# outdoor-sensor.net
KiCad netlist of a schematic drawn in EAGLE
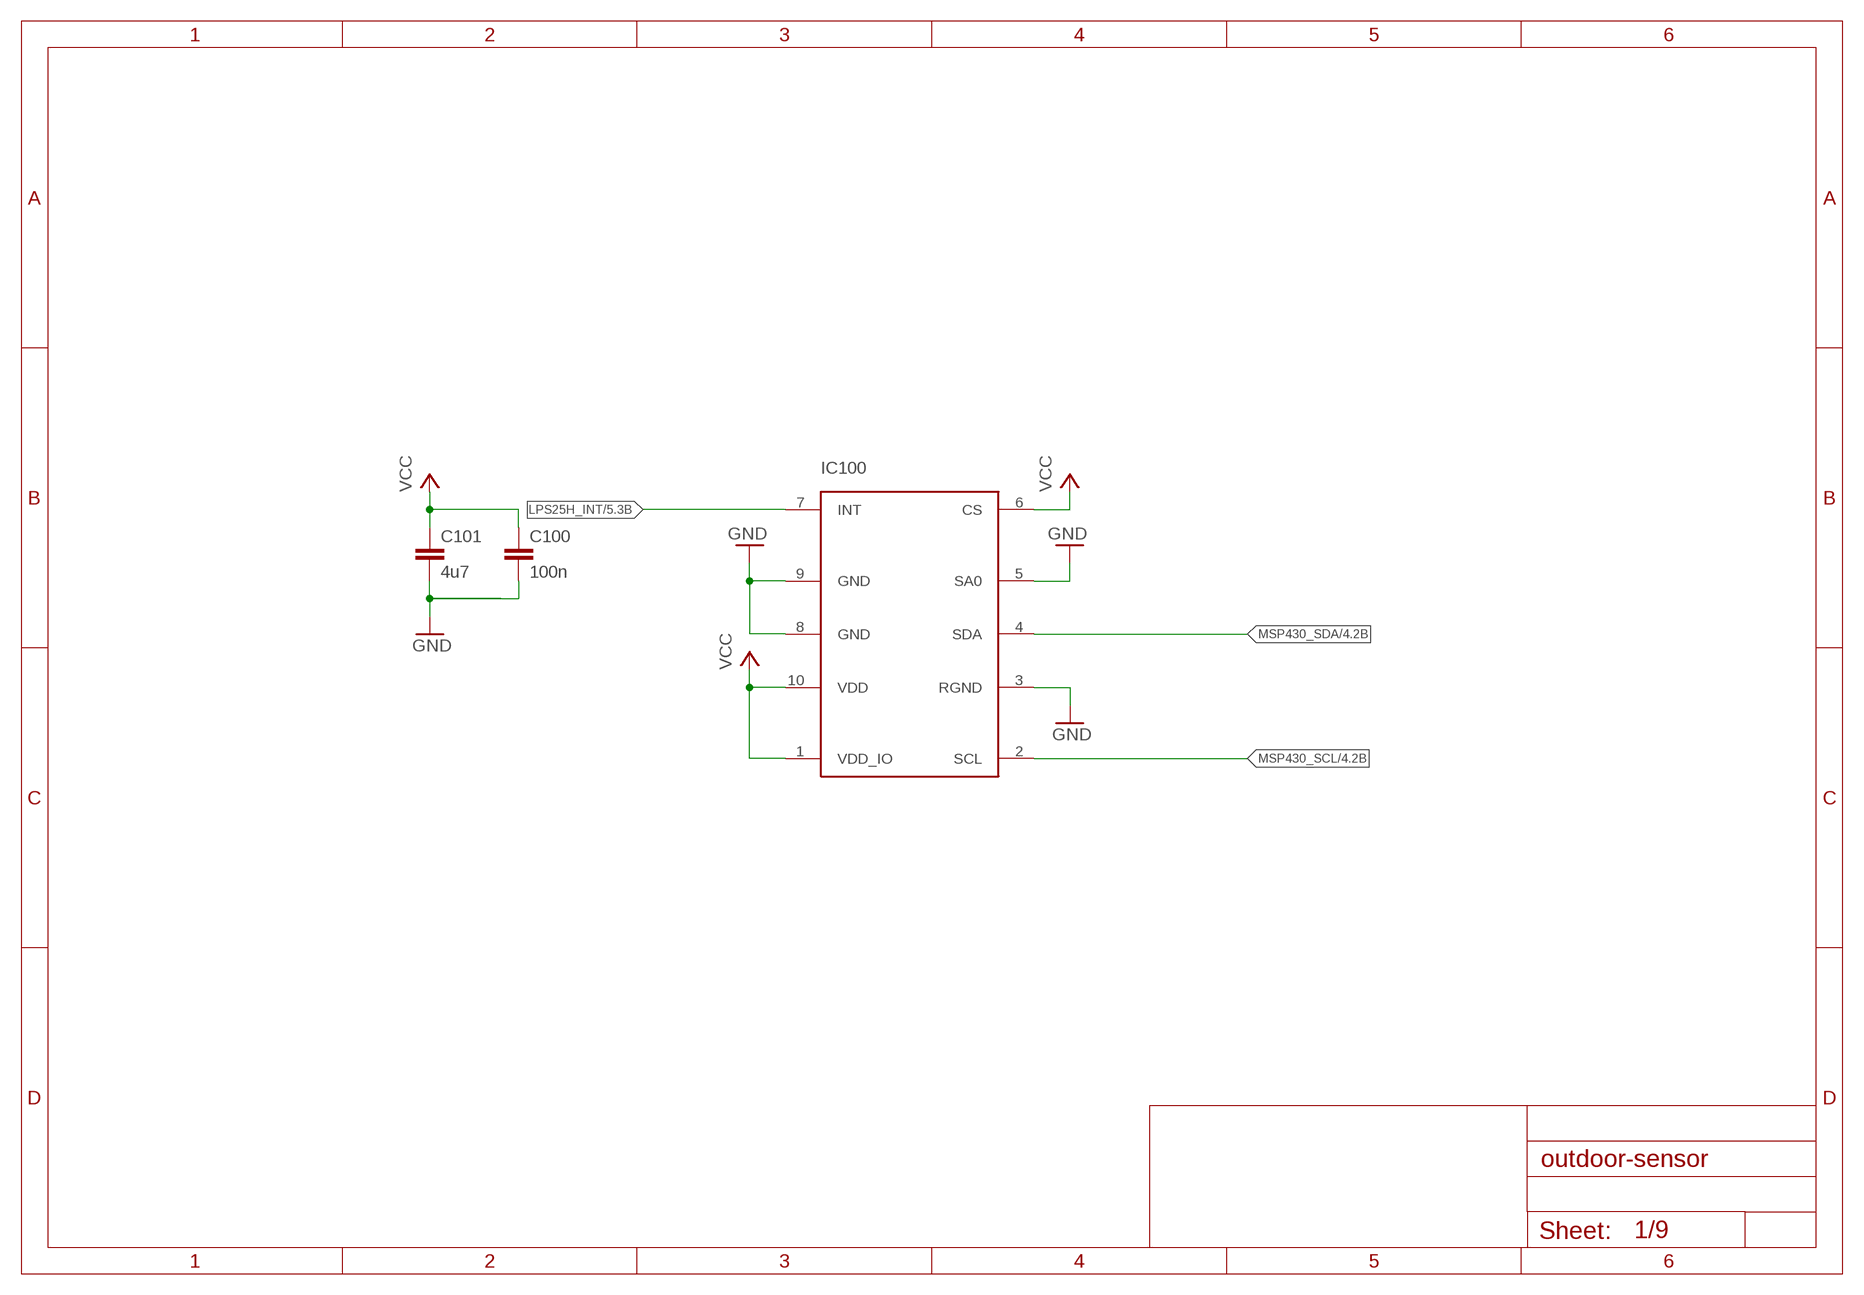
[diagram p0: schematic, sheet 1]
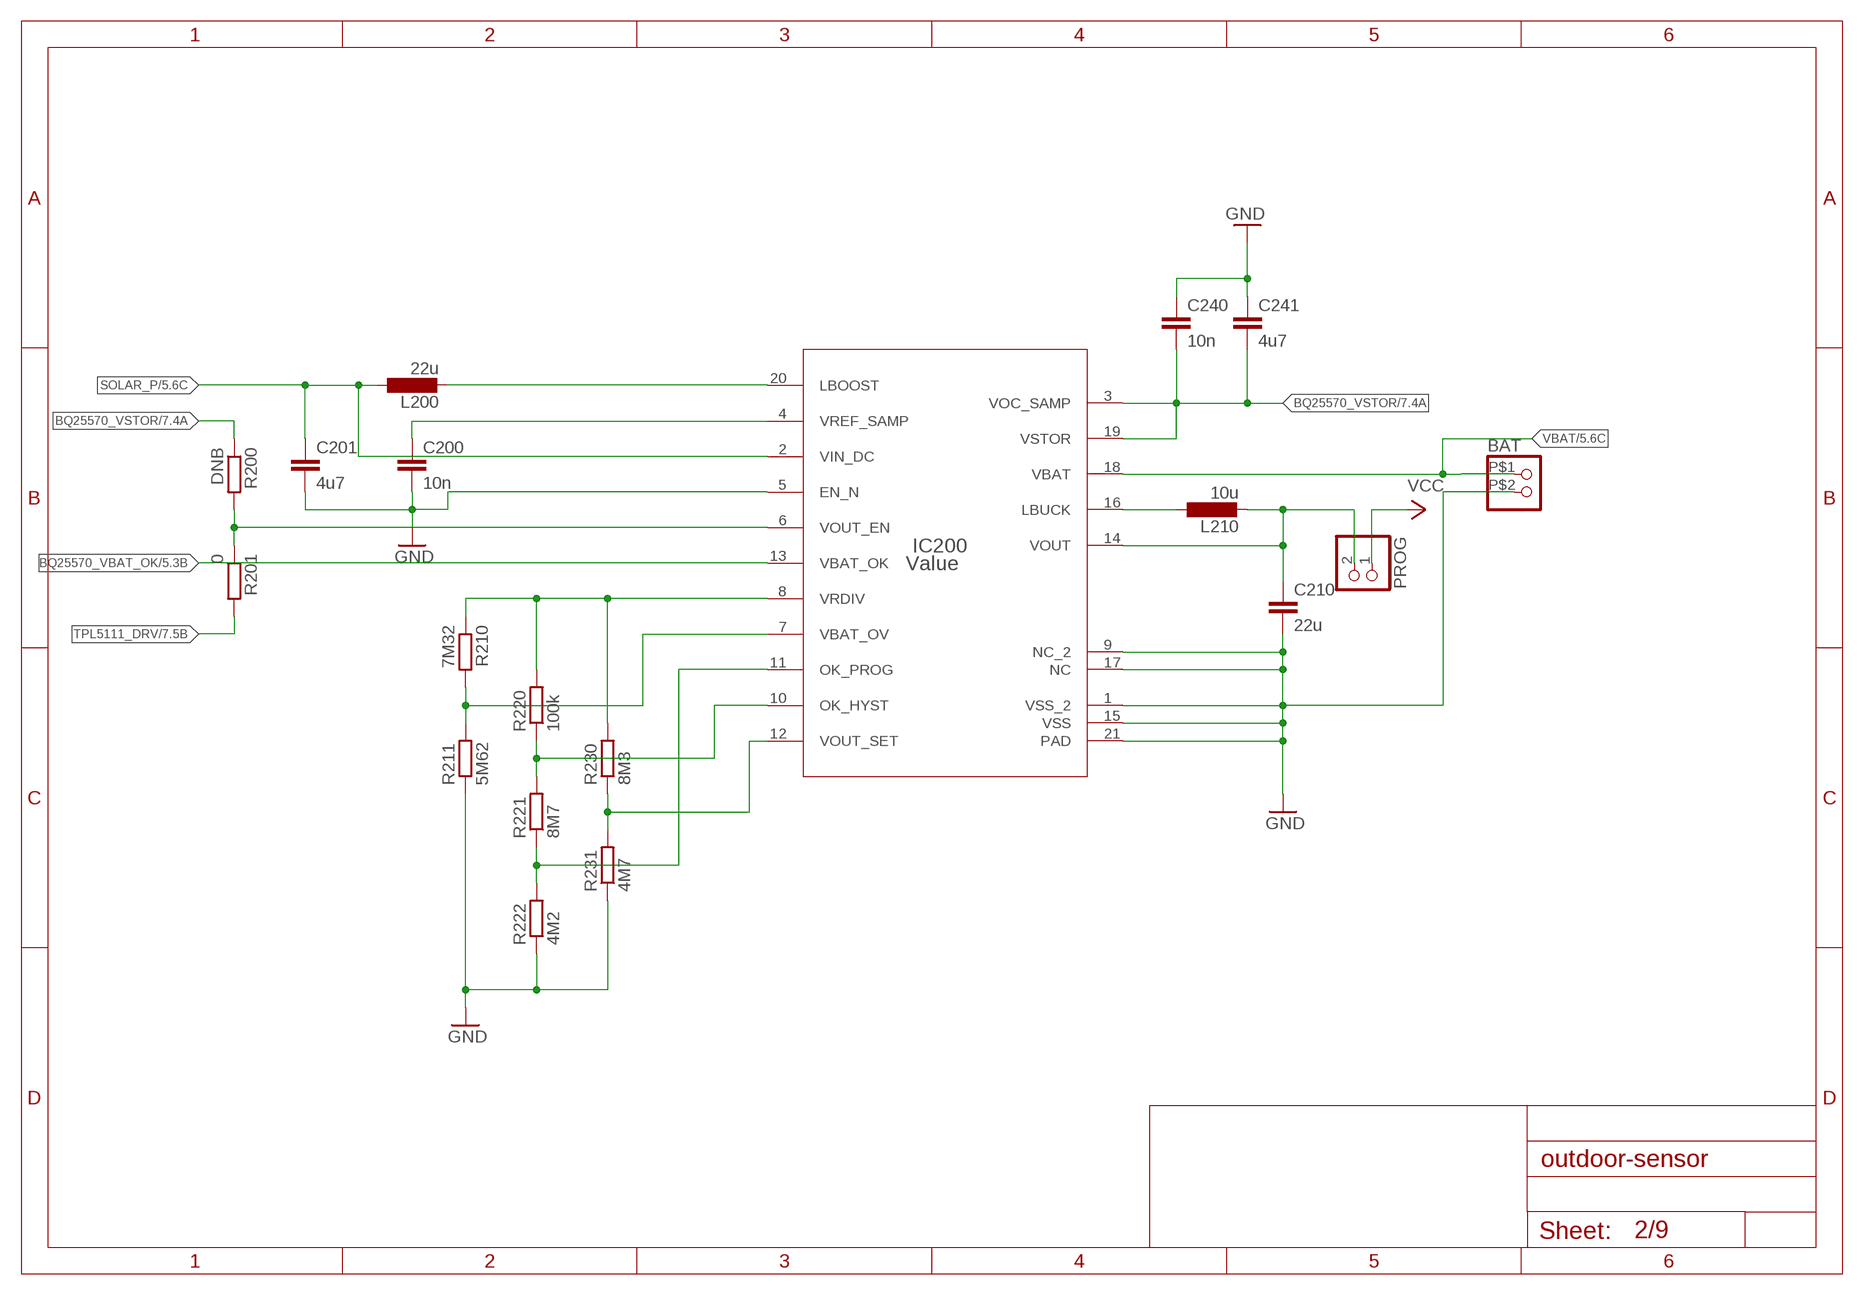
[diagram p1: schematic, sheet 2]
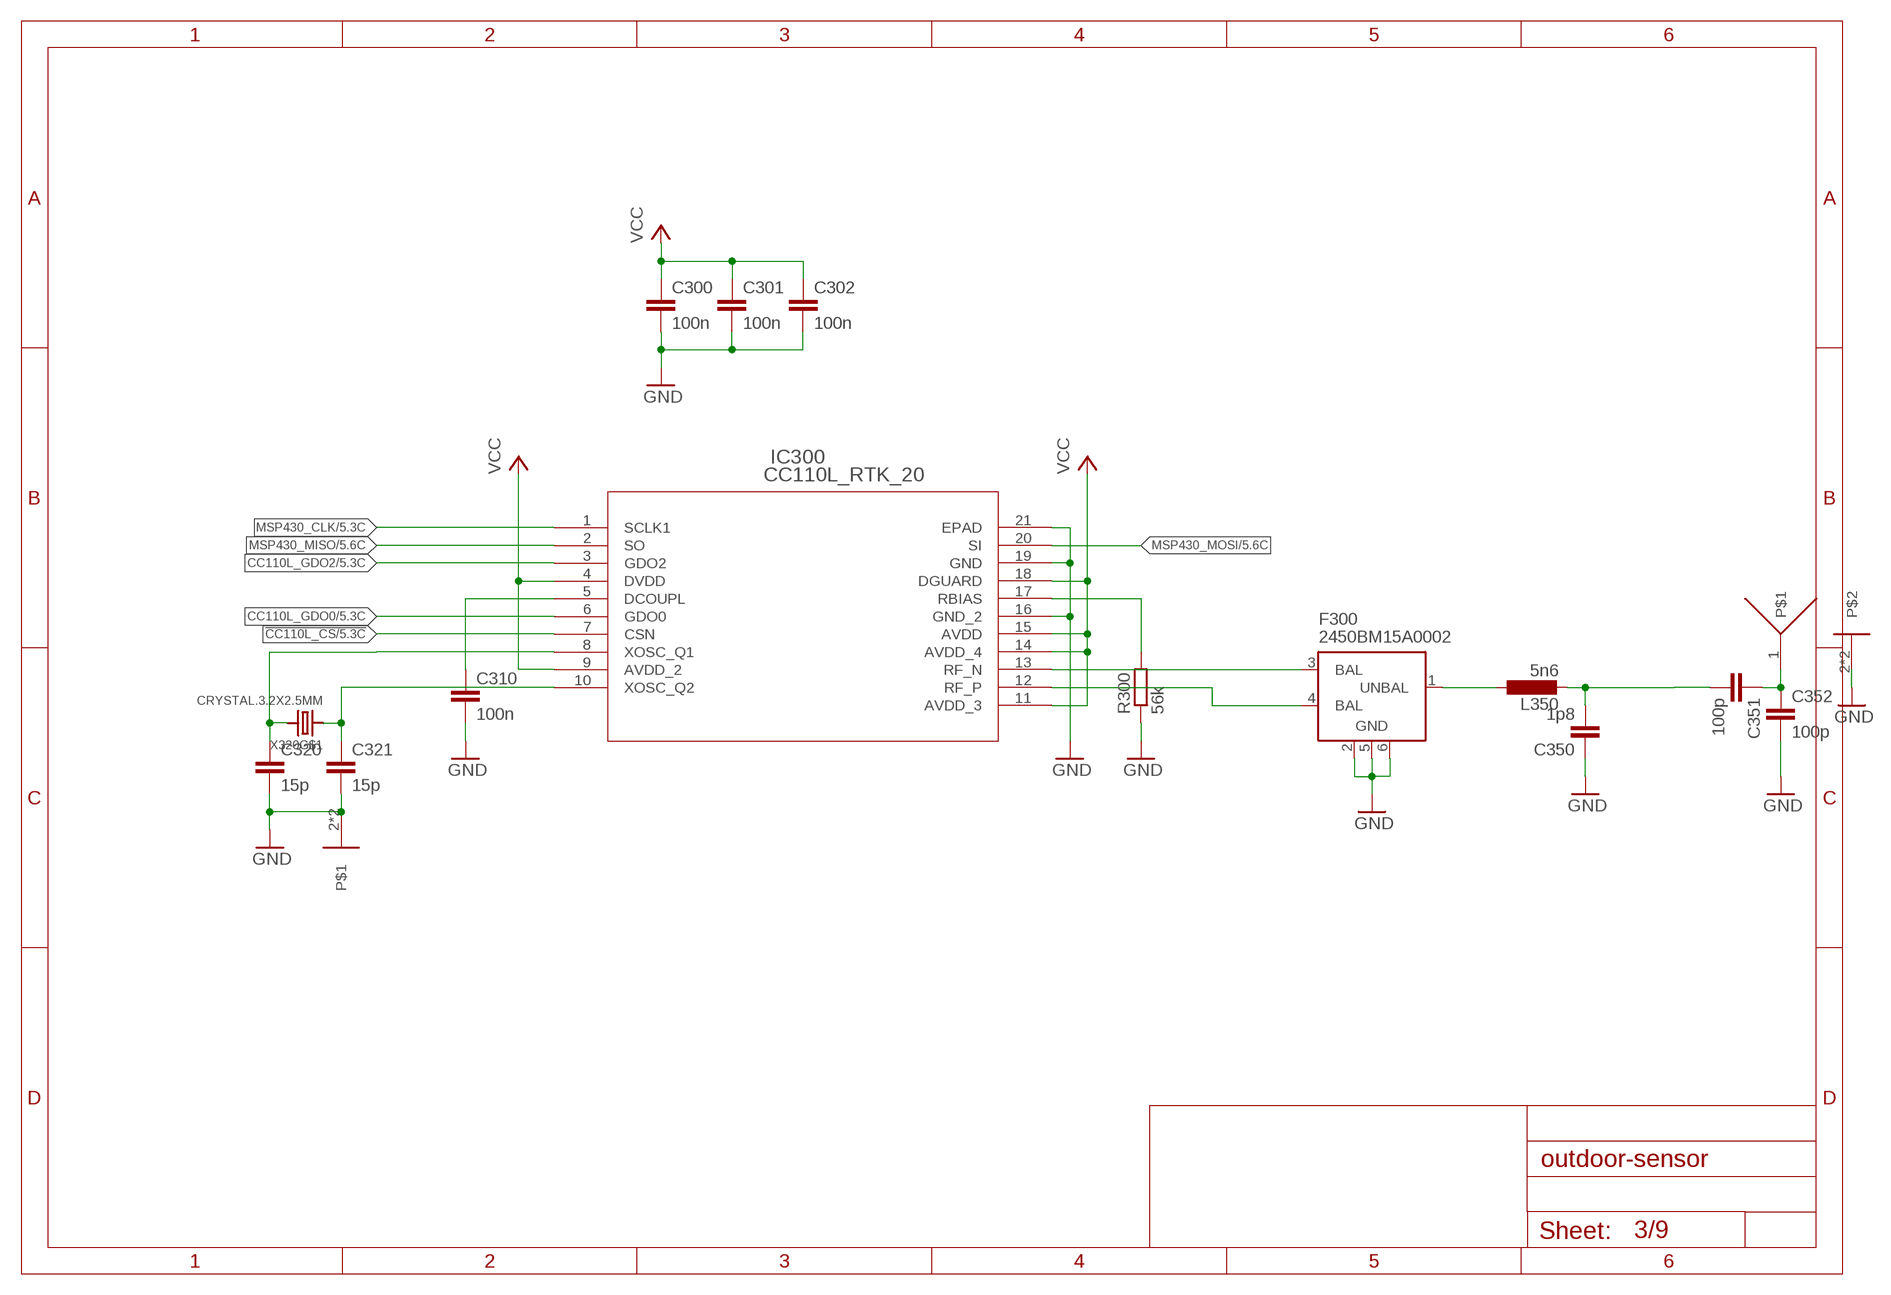
[diagram p2: schematic, sheet 3]
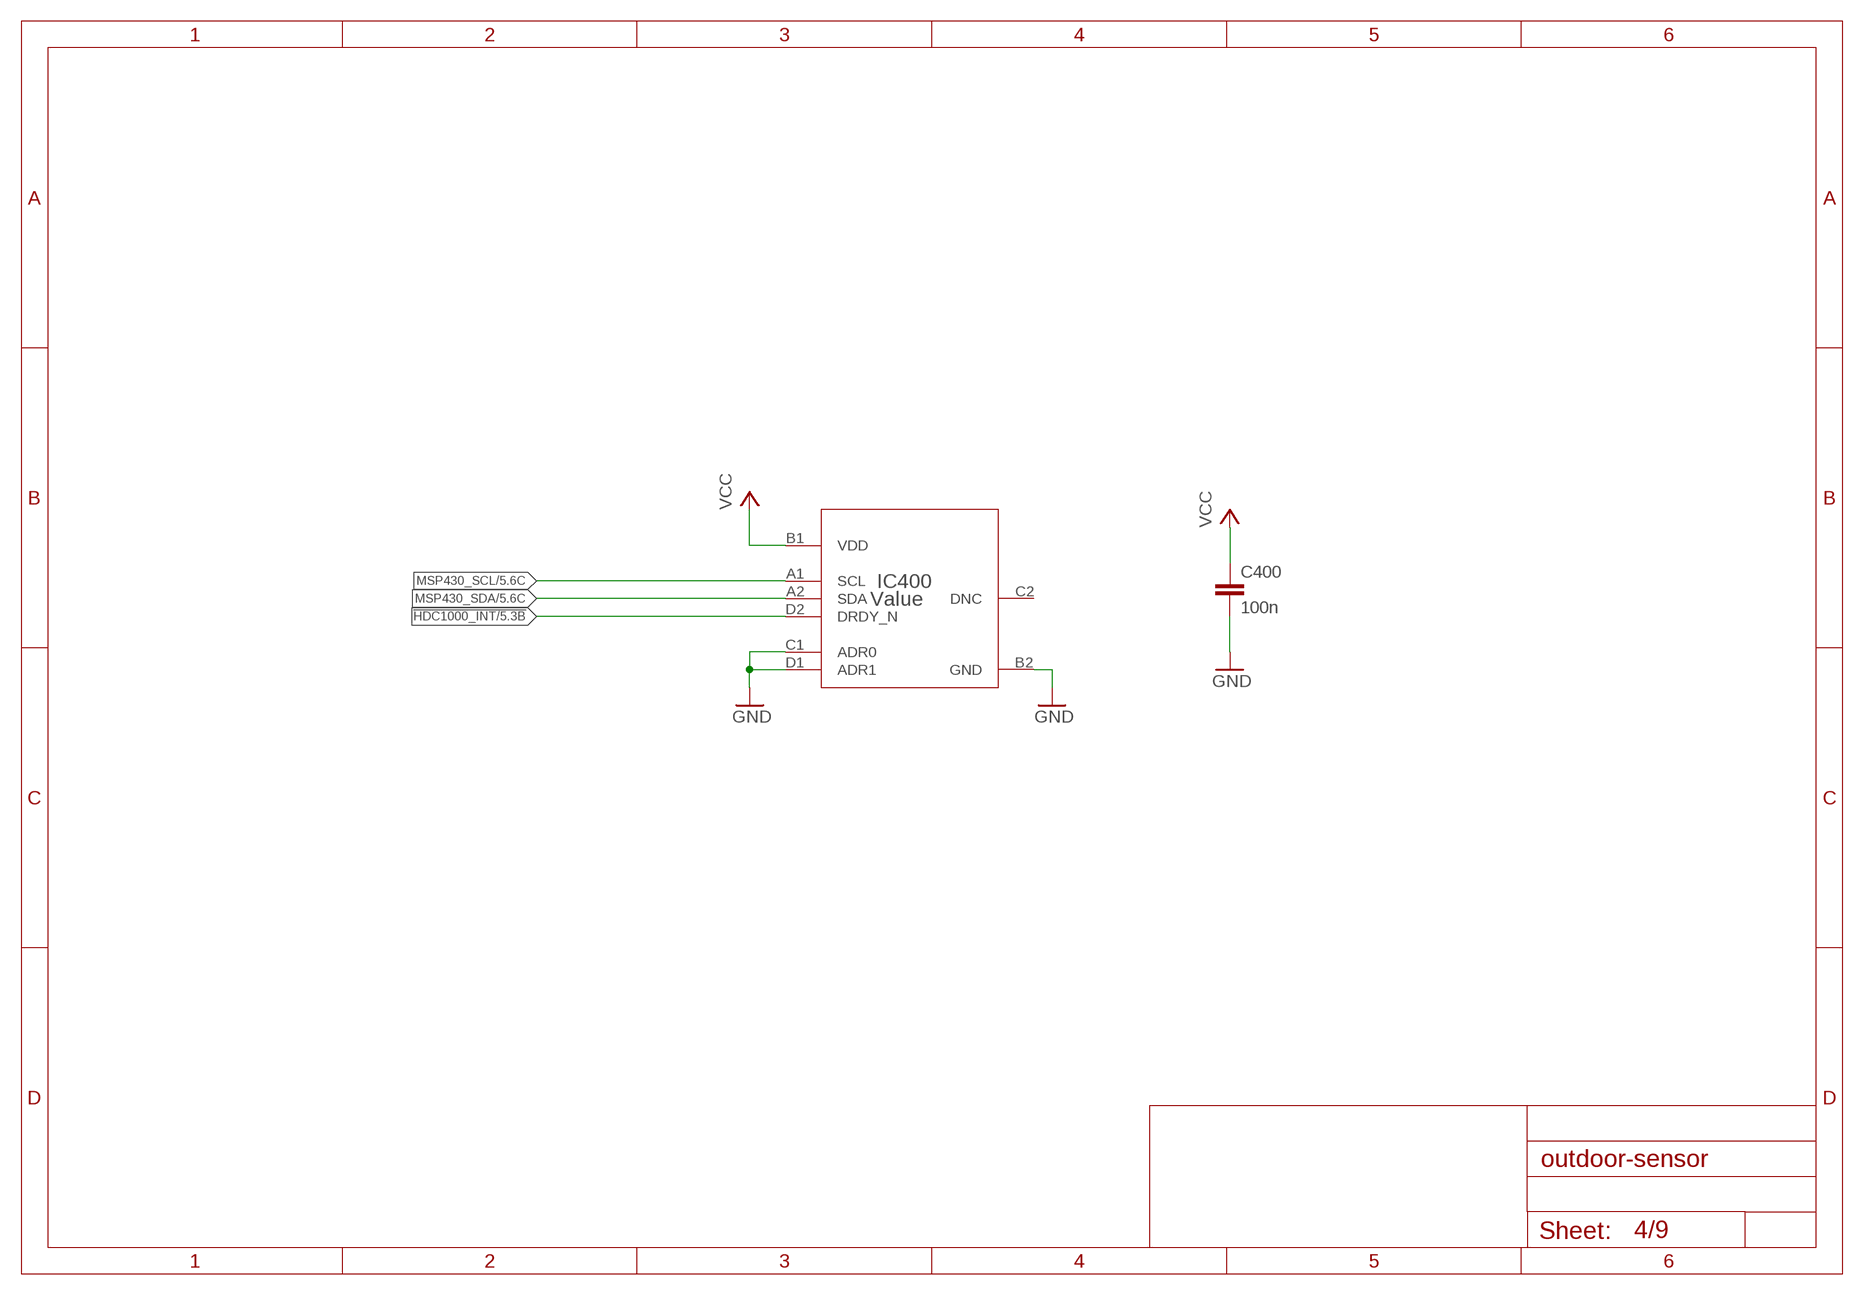
[diagram p3: schematic, sheet 4]
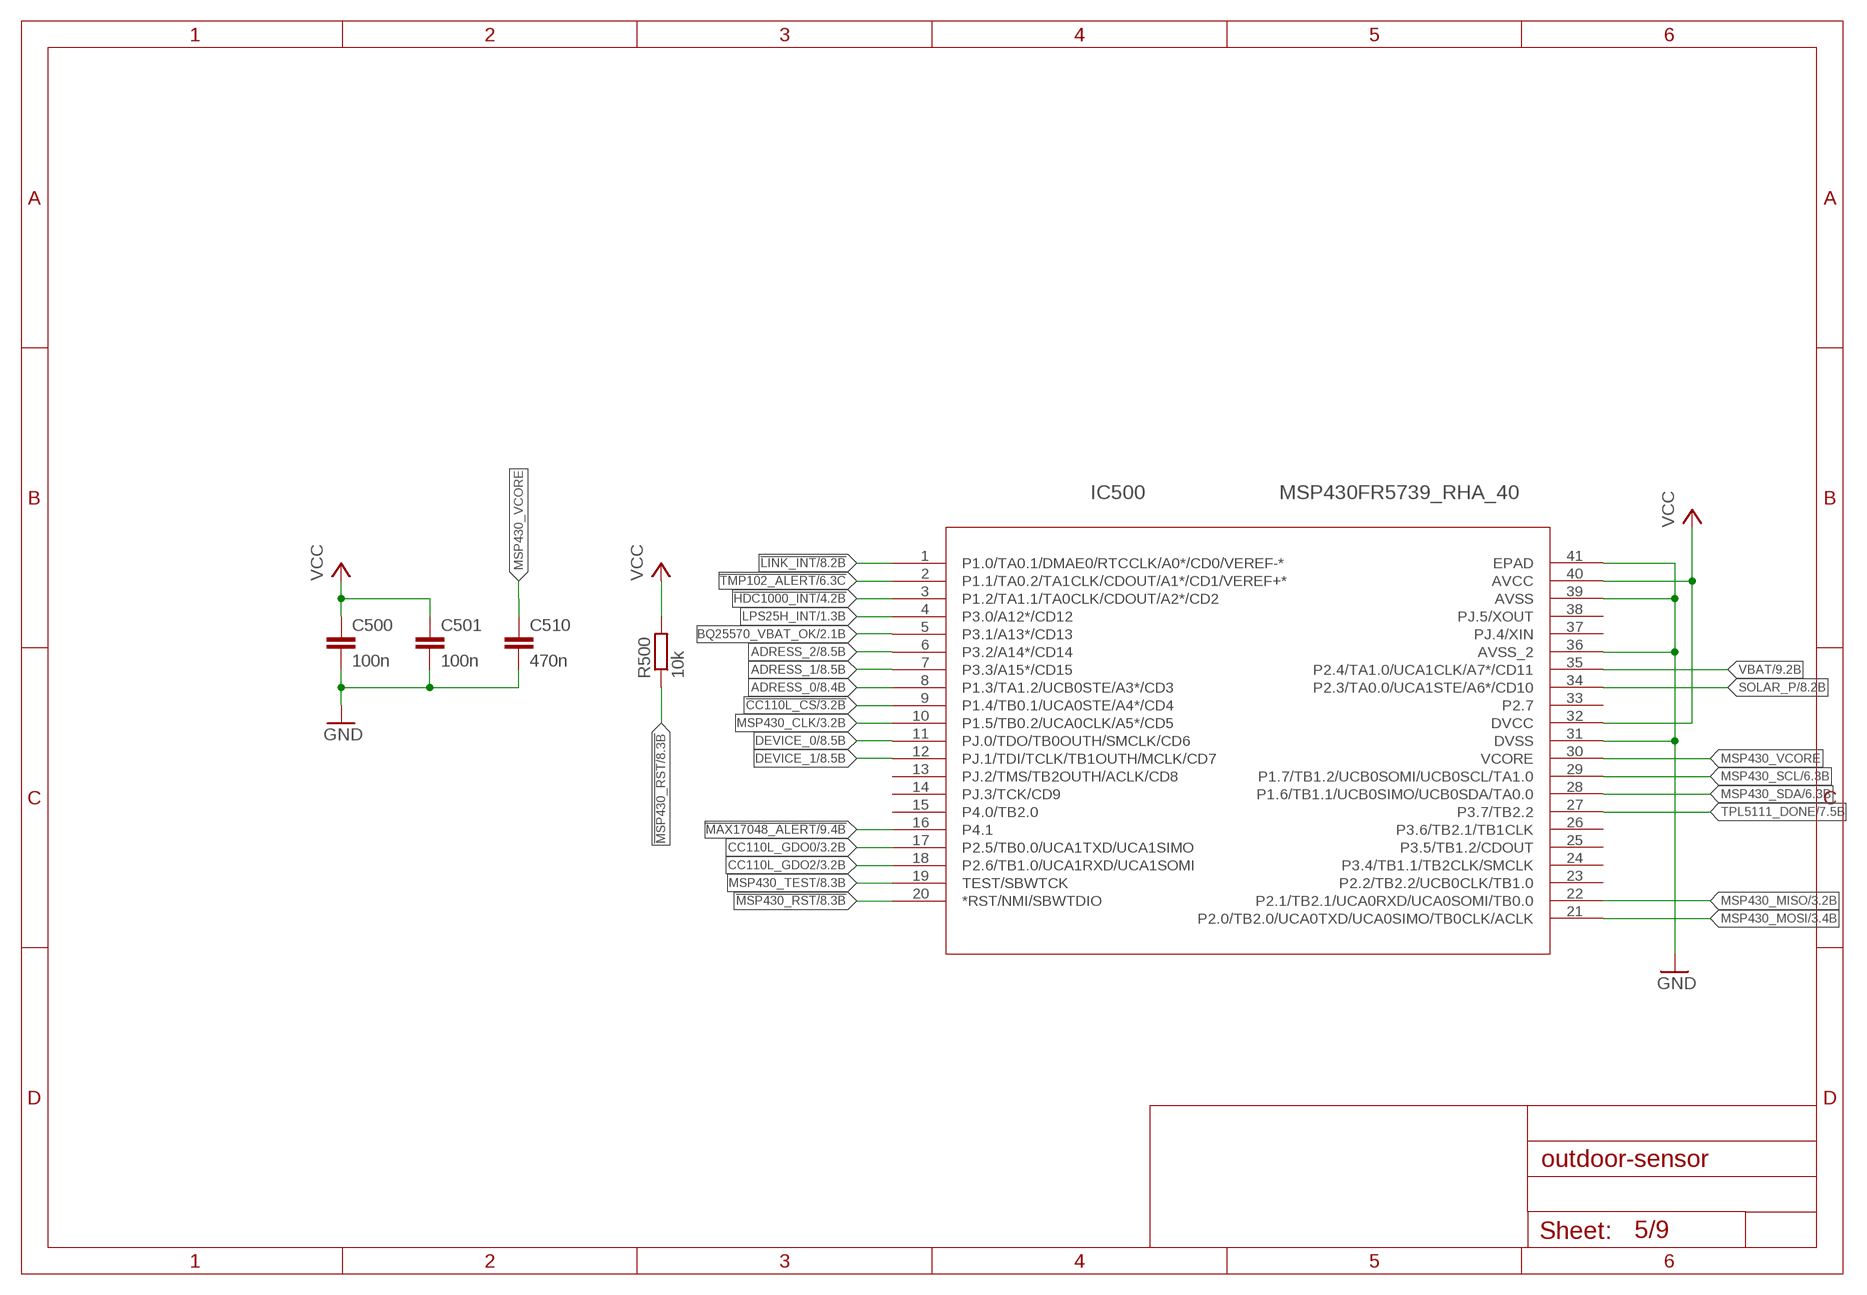
[diagram p4: schematic, sheet 5]
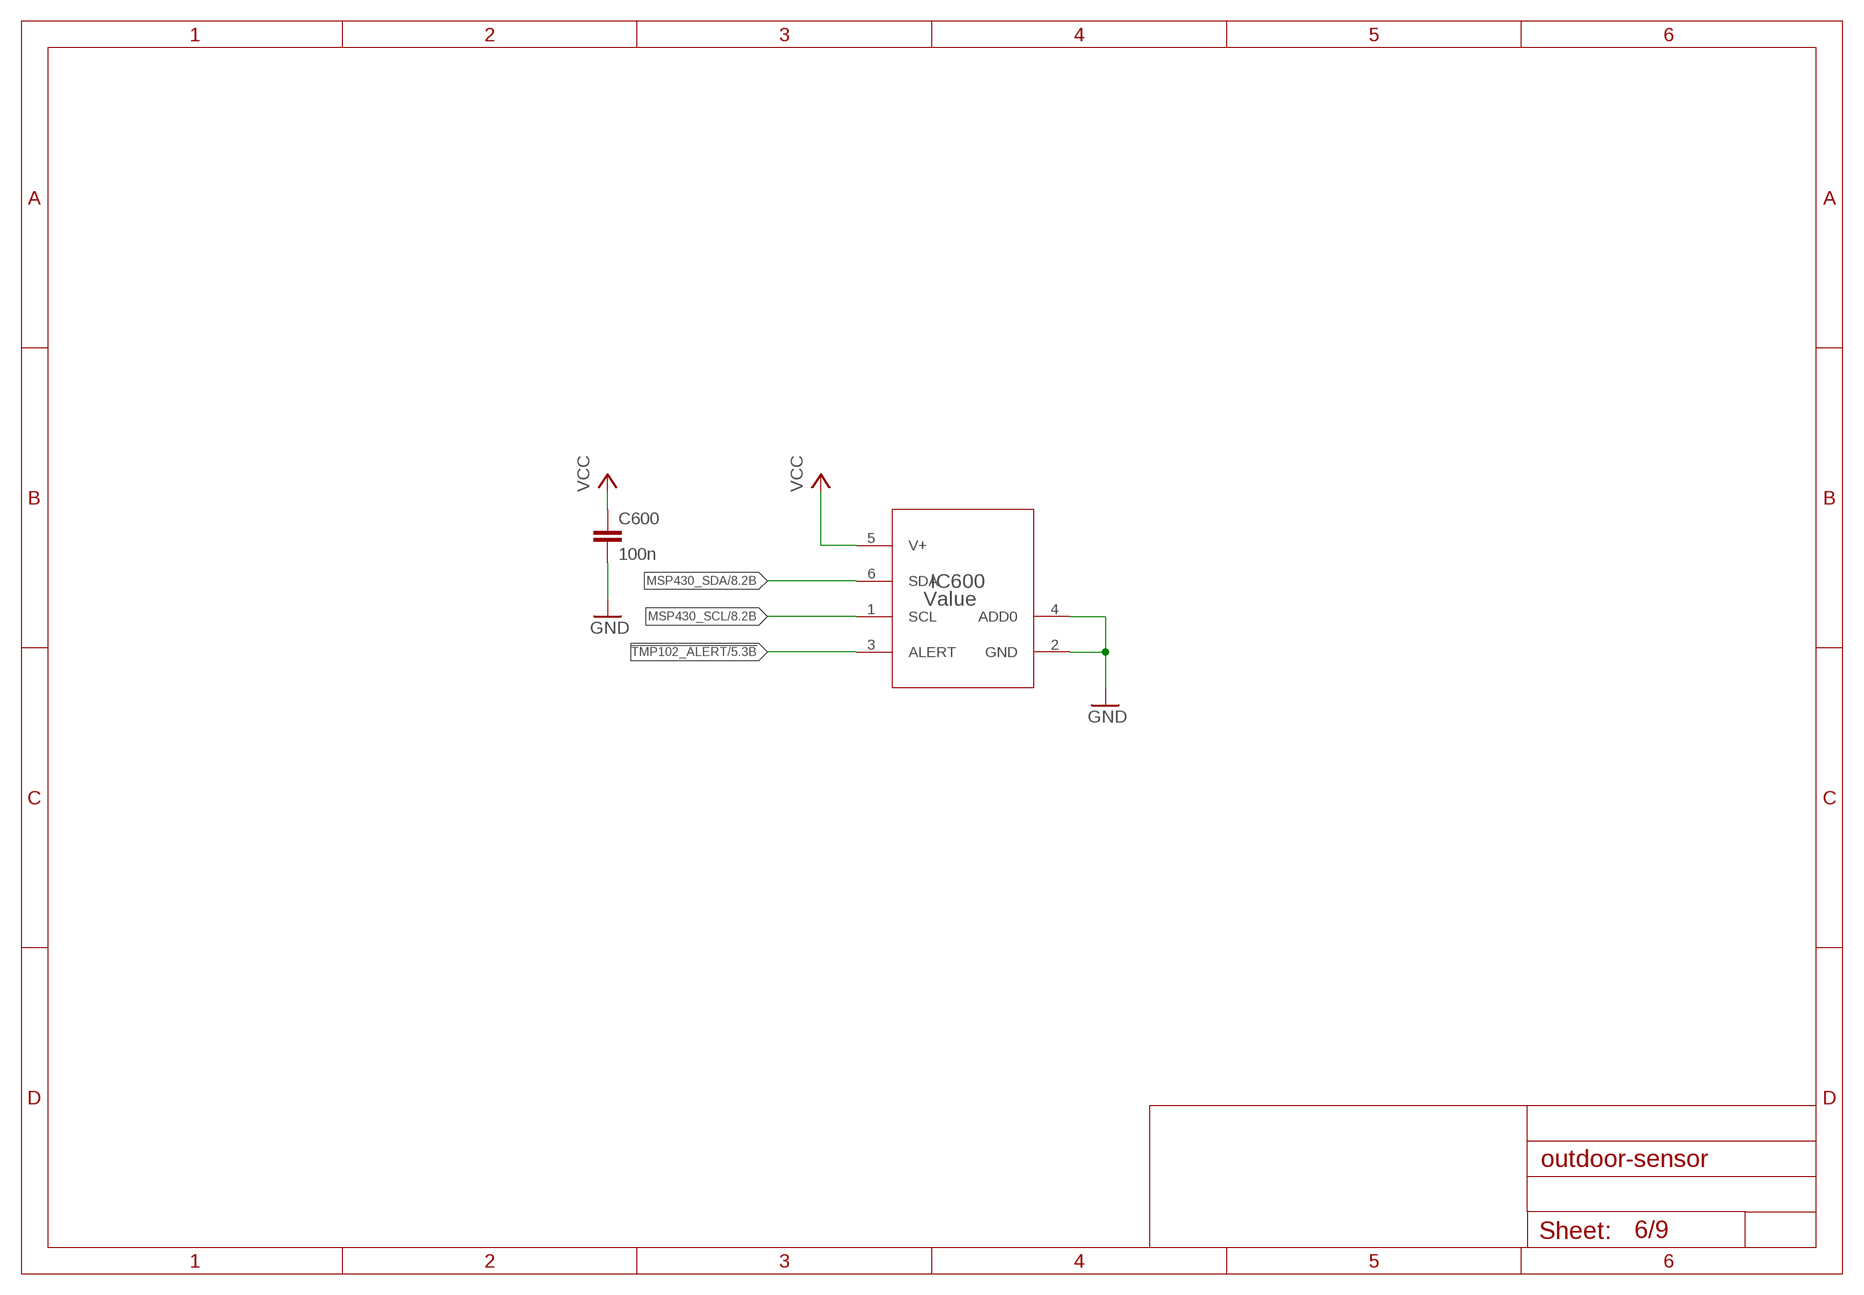
[diagram p5: schematic, sheet 6]
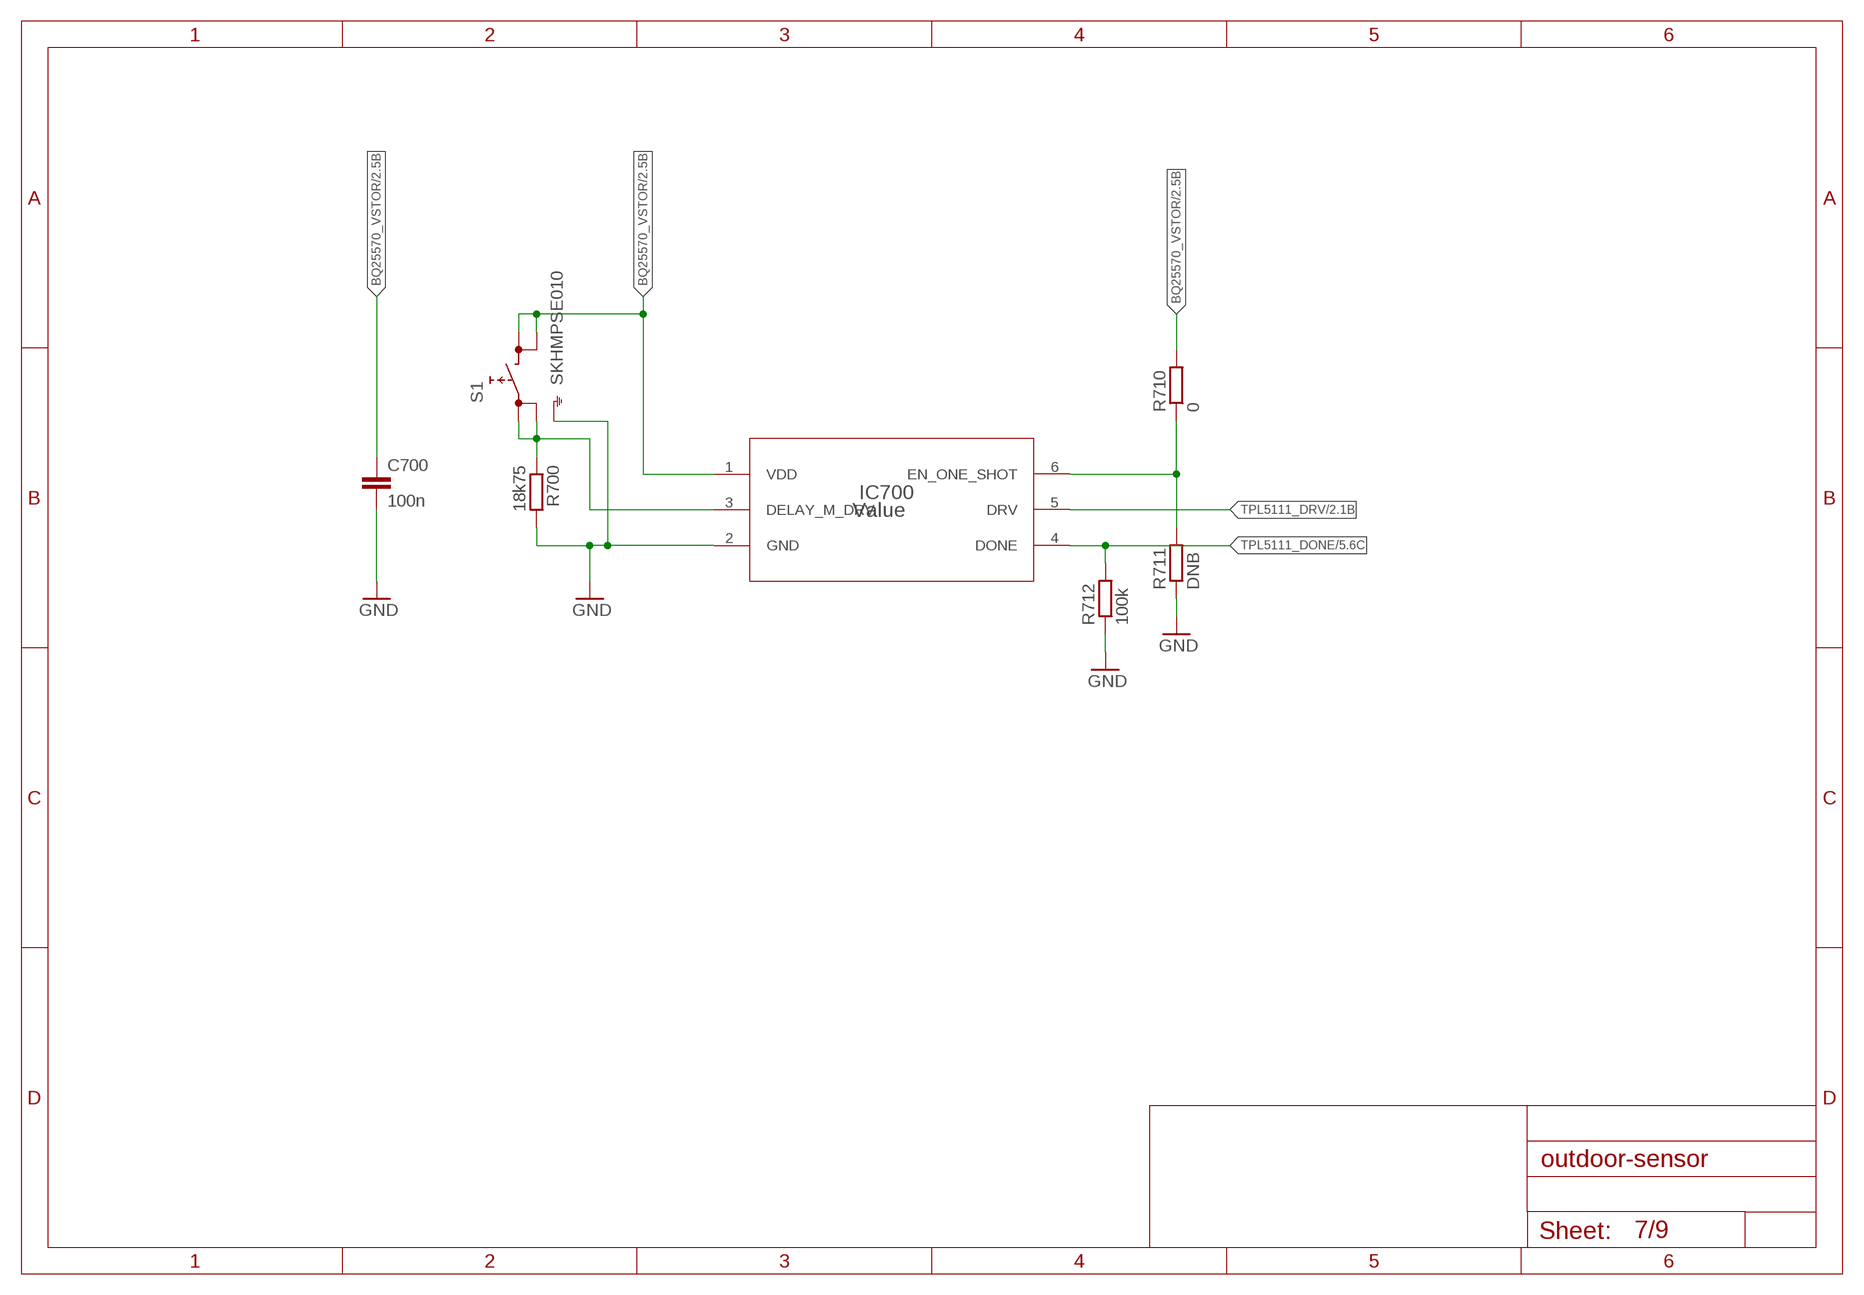
[diagram p6: schematic, sheet 7]
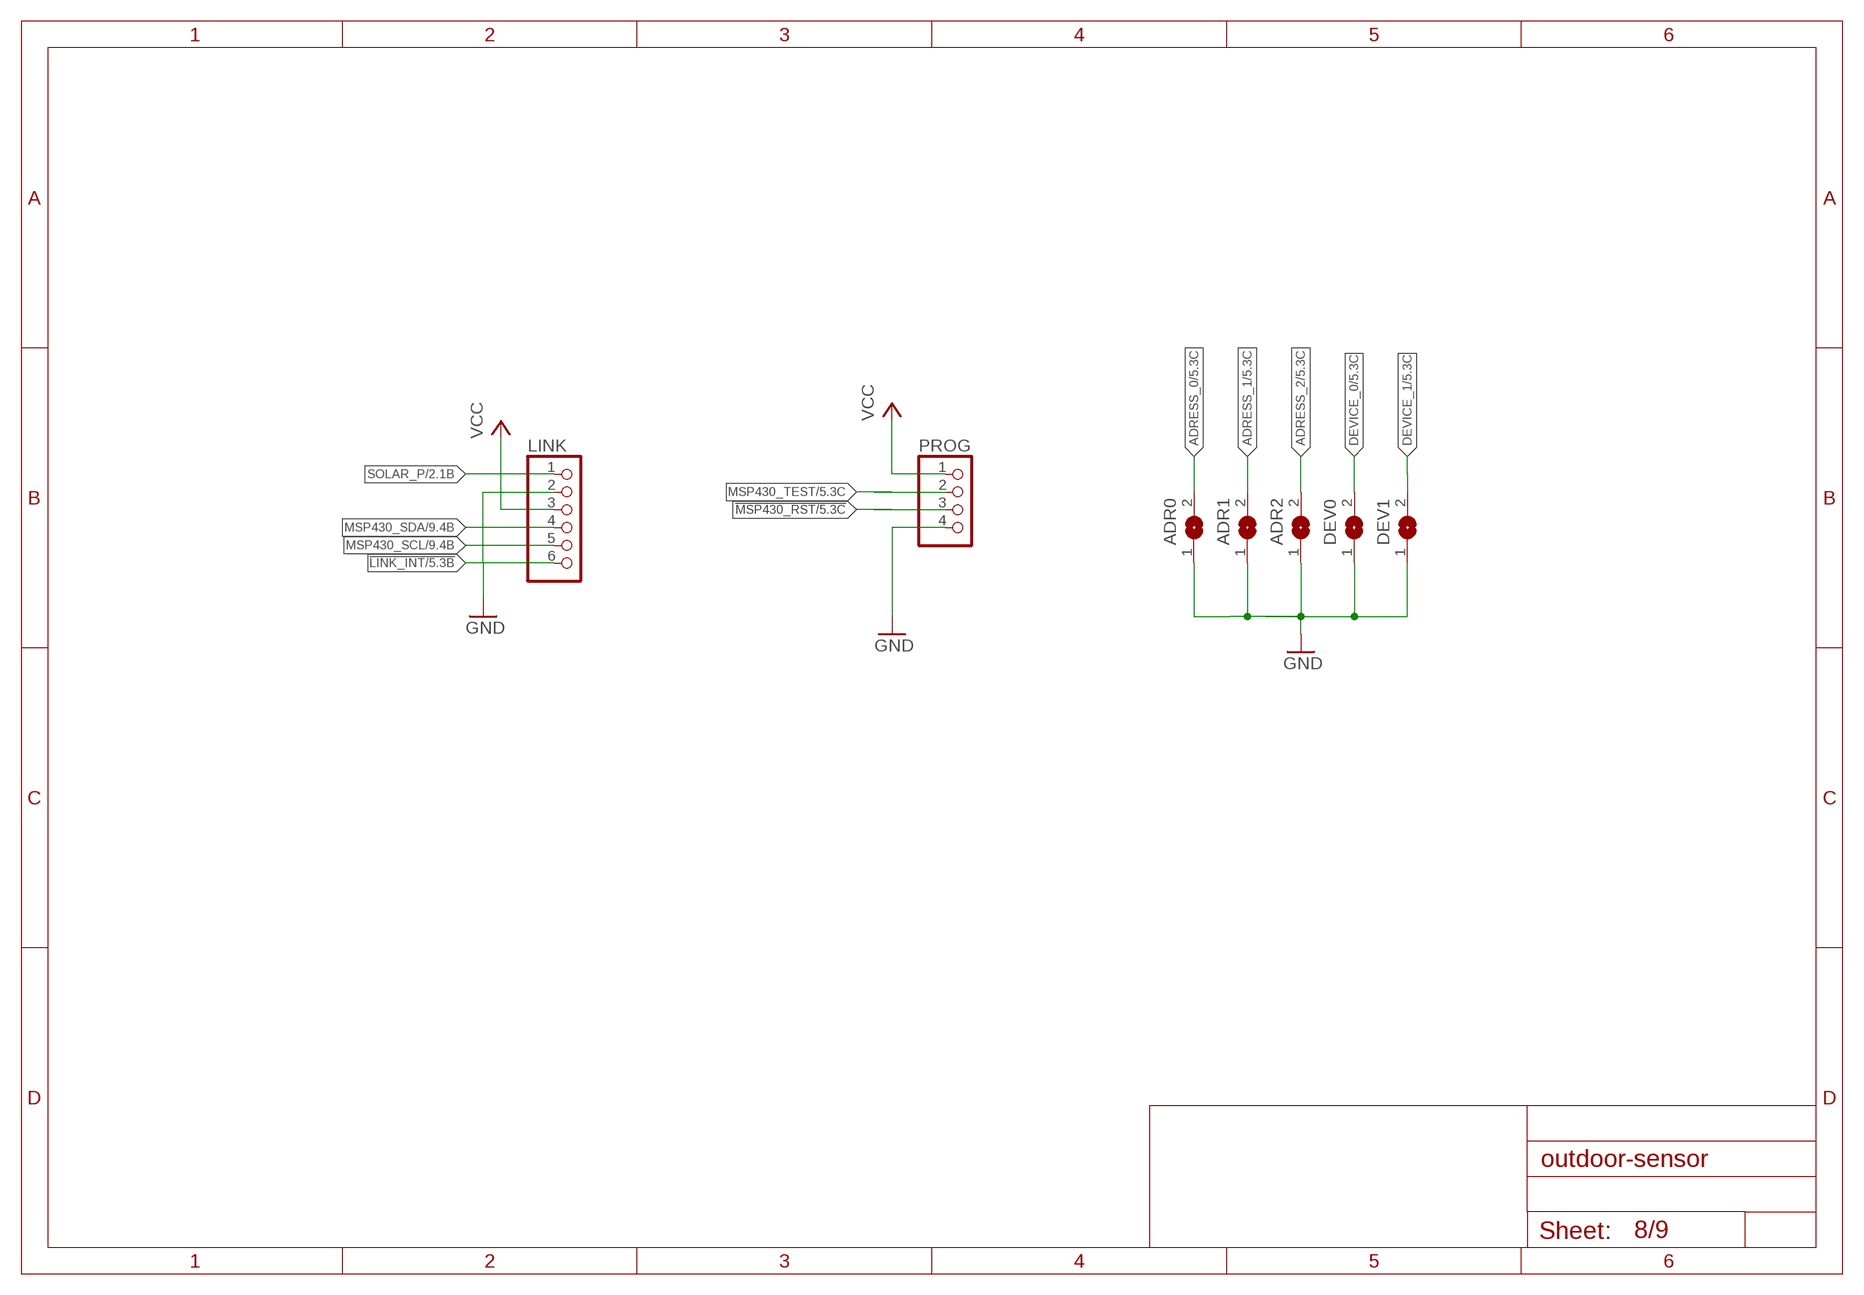
[diagram p7: schematic, sheet 8]
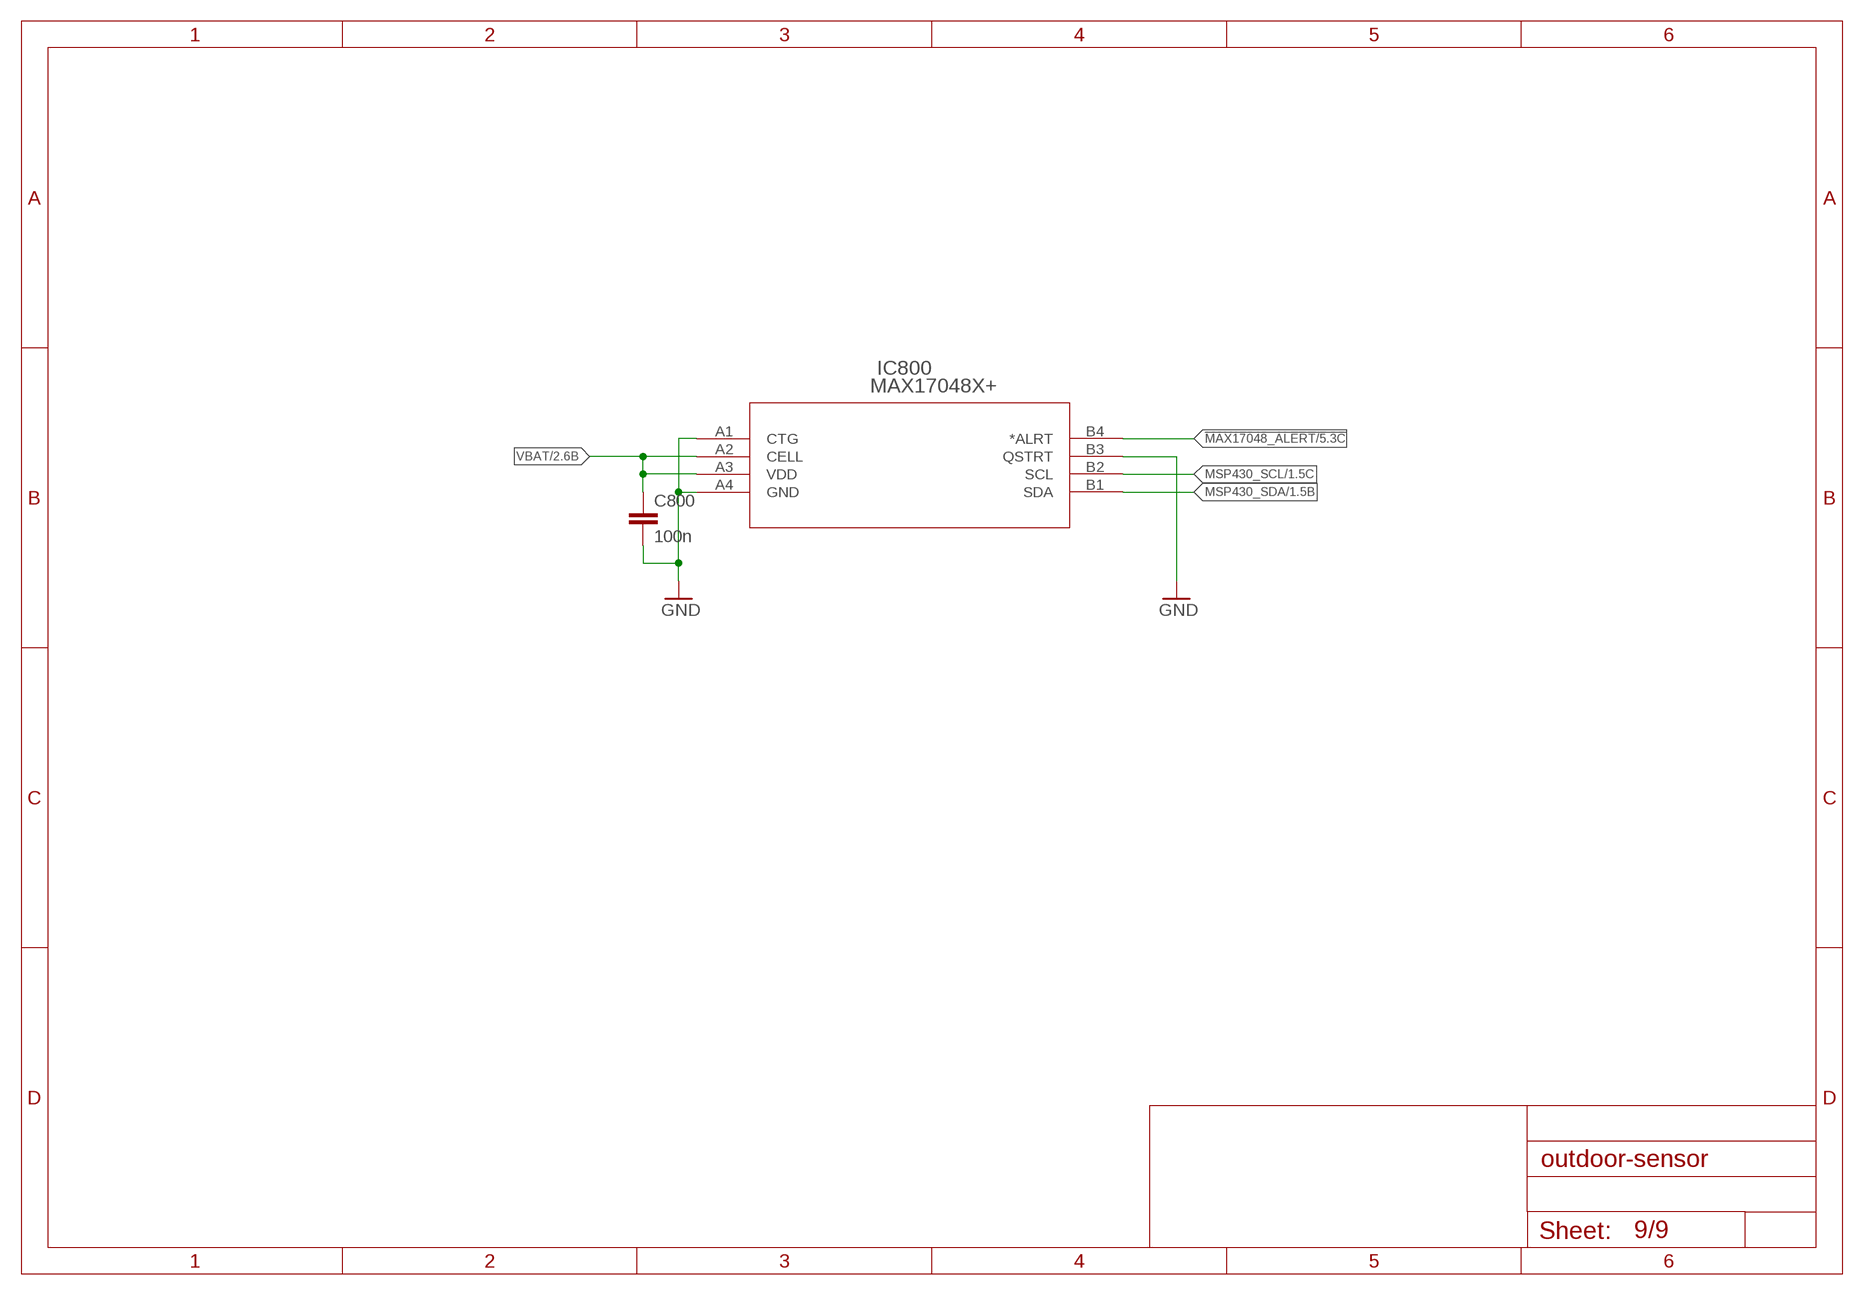
[diagram p8: schematic, sheet 9]

(export (version "E")
  (design (tool "Eeschema 10.0.6"))
  (components
    (comp (ref "ADR0")
      (value "SJW")
      (footprint "eagle-import:SJW")
      (libsource (lib "eagle-import") (part "SJW"))
    )
    (comp (ref "ADR1")
      (value "SJW")
      (footprint "eagle-import:SJW")
      (libsource (lib "eagle-import") (part "SJW"))
    )
    (comp (ref "ADR2")
      (value "SJW")
      (footprint "eagle-import:SJW")
      (libsource (lib "eagle-import") (part "SJW"))
    )
    (comp (ref "DEV0")
      (value "SJW")
      (footprint "eagle-import:SJW")
      (libsource (lib "eagle-import") (part "SJW"))
    )
    (comp (ref "DEV1")
      (value "SJW")
      (footprint "eagle-import:SJW")
      (libsource (lib "eagle-import") (part "SJW"))
    )
    (comp (ref "LINK")
      (value "PINHD-1X6")
      (footprint "eagle-import:1X06")
      (libsource (lib "eagle-import") (part "PINHD-1X6"))
    )
    (comp (ref "PROG")
      (value "PINHD-1X4")
      (footprint "eagle-import:1X04")
      (libsource (lib "eagle-import") (part "PINHD-1X4"))
    )
    (comp (ref "!PROG")
      (value "PINHD-1X2")
      (footprint "eagle-import:1X02")
      (libsource (lib "eagle-import") (part "PINHD-1X2"))
    )
    (comp (ref "BAT")
      (value "PINHD-1X2IPBS-102-01-T-S-GP")
      (footprint "eagle-import:IPBS-102-01-T-S-GP")
      (libsource (lib "eagle-import") (part "PINHD-1X2IPBS-102-01-T-S-GP"))
    )
    (comp (ref "C200")
      (value "10n")
      (footprint "eagle-import:C0603")
      (libsource (lib "eagle-import") (part "C-EUC0603"))
    )
    (comp (ref "C201")
      (value "4u7")
      (footprint "eagle-import:C0603")
      (libsource (lib "eagle-import") (part "C-EUC0603"))
    )
    (comp (ref "C210")
      (value "22u")
      (footprint "eagle-import:C0603")
      (fields (field (name "MF") "AVX") (field (name "MPN") "06034D226MAT2A"))
      (libsource (lib "eagle-import") (part "C-EUC0603"))
    )
    (comp (ref "C240")
      (value "10n")
      (footprint "eagle-import:C0603")
      (libsource (lib "eagle-import") (part "C-EUC0603"))
    )
    (comp (ref "C241")
      (value "4u7")
      (footprint "eagle-import:C0603")
      (libsource (lib "eagle-import") (part "C-EUC0603"))
    )
    (comp (ref "IC200")
      (value "Value")
      (footprint "eagle-import:RGR0020A")
      (fields
        (field (name "ALTERNATEPARTNUMBER") "BQ25570RGRT")
        (field (name "MANUFACTURER") "Texas Instruments")
        (field (name "PARTNUMBER") "BQ25570RGRR")
      )
      (libsource (lib "eagle-import") (part "BQ25570RGRR"))
    )
    (comp (ref "L200")
      (value "22u")
      (footprint "eagle-import:L3944")
      (libsource (lib "eagle-import") (part "L-EUL3944"))
    )
    (comp (ref "L210")
      (value "10u")
      (footprint "eagle-import:L2.5X2.0")
      (libsource (lib "eagle-import") (part "L-EUM"))
    )
    (comp (ref "R200")
      (value "DNB")
      (footprint "eagle-import:R0603")
      (libsource (lib "eagle-import") (part "R-EU_R0603"))
    )
    (comp (ref "R201")
      (value "0")
      (footprint "eagle-import:R0603")
      (libsource (lib "eagle-import") (part "R-EU_R0603"))
    )
    (comp (ref "R210")
      (value "7M32")
      (footprint "eagle-import:R0603")
      (libsource (lib "eagle-import") (part "R-EU_R0603"))
    )
    (comp (ref "R211")
      (value "5M62")
      (footprint "eagle-import:R0603")
      (libsource (lib "eagle-import") (part "R-EU_R0603"))
    )
    (comp (ref "R220")
      (value "100k")
      (footprint "eagle-import:R0603")
      (libsource (lib "eagle-import") (part "R-EU_R0603"))
    )
    (comp (ref "R221")
      (value "8M7")
      (footprint "eagle-import:R0603")
      (libsource (lib "eagle-import") (part "R-EU_R0603"))
    )
    (comp (ref "R222")
      (value "4M2")
      (footprint "eagle-import:R0603")
      (libsource (lib "eagle-import") (part "R-EU_R0603"))
    )
    (comp (ref "R230")
      (value "8M3")
      (footprint "eagle-import:R0603")
      (libsource (lib "eagle-import") (part "R-EU_R0603"))
    )
    (comp (ref "R231")
      (value "4M7")
      (footprint "eagle-import:R0603")
      (libsource (lib "eagle-import") (part "R-EU_R0603"))
    )
    (comp (ref "C500")
      (value "100n")
      (footprint "eagle-import:C0603")
      (fields (field (name "MF") "STMICROELECTRONICS") (field (name "MPN") "STP100NF04"))
      (libsource (lib "eagle-import") (part "C-EUC0603"))
    )
    (comp (ref "C501")
      (value "100n")
      (footprint "eagle-import:C0603")
      (fields (field (name "MF") "STMICROELECTRONICS") (field (name "MPN") "STP100NF04"))
      (libsource (lib "eagle-import") (part "C-EUC0603"))
    )
    (comp (ref "C510")
      (value "470n")
      (footprint "eagle-import:C0603")
      (libsource (lib "eagle-import") (part "C-EUC0603"))
    )
    (comp (ref "IC500")
      (value "MSP430FR5739_RHA_40")
      (footprint "eagle-import:RHA40_2P9X2P9")
      (fields
        (field (name "GENERIC_PART_NUMBER") "MSP430FR5739")
        (field (name "MANUFACTURER") "Texas Instruments")
        (field (name "MANUFACTURER_PART_NUMBER") "msp430fr5739_rha_40")
      )
      (libsource (lib "eagle-import") (part "MSP430FR5739_RHA_40"))
    )
    (comp (ref "R500")
      (value "10k")
      (footprint "eagle-import:R0603")
      (libsource (lib "eagle-import") (part "R-EU_R0603"))
    )
    (comp (ref "C100")
      (value "100n")
      (footprint "eagle-import:C0603")
      (fields (field (name "MF") "STMICROELECTRONICS") (field (name "MPN") "STP100NF04"))
      (libsource (lib "eagle-import") (part "C-EUC0603"))
    )
    (comp (ref "C101")
      (value "4u7")
      (footprint "eagle-import:C0603")
      (libsource (lib "eagle-import") (part "C-EUC0603"))
    )
    (comp (ref "IC100")
      (value "LPS25H")
      (footprint "eagle-import:LPS25H")
      (fields (field (name "MF") "STMICROELECTRONICS") (field (name "MPN") "LPS25HBTR"))
      (libsource (lib "eagle-import") (part "LPS25H"))
    )
    (comp (ref "C600")
      (value "100n")
      (footprint "eagle-import:C0603")
      (fields (field (name "MF") "STMICROELECTRONICS") (field (name "MPN") "STP100NF04"))
      (libsource (lib "eagle-import") (part "C-EUC0603"))
    )
    (comp (ref "IC600")
      (value "Value")
      (footprint "eagle-import:DRL0006A")
      (fields (field (name "MANUFACTURER") "Texas Instruments") (field (name "PARTNUMBER") "TMP102AQDRLRQ1"))
      (libsource (lib "eagle-import") (part "TMP102AQDRLRQ1"))
    )
    (comp (ref "C800")
      (value "100n")
      (footprint "eagle-import:C0603")
      (libsource (lib "eagle-import") (part "C-EUC0603"))
    )
    (comp (ref "IC800")
      (value "MAX17048X+")
      (footprint "eagle-import:21-0555B_W80B1-1")
      (fields (field (name "MANUFACTURER_PART_NUMBER") "max17048x+"))
      (libsource (lib "eagle-import") (part "MAX17048X+"))
    )
    (comp (ref "C400")
      (value "100n")
      (footprint "eagle-import:C0603")
      (fields (field (name "MF") "STMICROELECTRONICS") (field (name "MPN") "STP100NF04"))
      (libsource (lib "eagle-import") (part "C-EUC0603"))
    )
    (comp (ref "IC400")
      (value "Value")
      (footprint "eagle-import:YPA0008AGAE")
      (fields
        (field (name "ALTERNATEPARTNUMBER") "HDC1000YPAT")
        (field (name "MANUFACTURER") "Texas Instruments")
        (field (name "PARTNUMBER") "HDC1000YPAR")
      )
      (libsource (lib "eagle-import") (part "HDC1000YPAR"))
    )
    (comp (ref "C300")
      (value "100n")
      (footprint "eagle-import:C0603")
      (fields (field (name "MF") "STMICROELECTRONICS") (field (name "MPN") "STP100NF04"))
      (libsource (lib "eagle-import") (part "C-EUC0603"))
    )
    (comp (ref "C301")
      (value "100n")
      (footprint "eagle-import:C0603")
      (fields (field (name "MF") "STMICROELECTRONICS") (field (name "MPN") "STP100NF04"))
      (libsource (lib "eagle-import") (part "C-EUC0603"))
    )
    (comp (ref "C302")
      (value "100n")
      (footprint "eagle-import:C0603")
      (fields (field (name "MF") "STMICROELECTRONICS") (field (name "MPN") "STP100NF04"))
      (libsource (lib "eagle-import") (part "C-EUC0603"))
    )
    (comp (ref "C310")
      (value "100n")
      (footprint "eagle-import:C0603")
      (fields (field (name "MF") "STMICROELECTRONICS") (field (name "MPN") "STP100NF04"))
      (libsource (lib "eagle-import") (part "C-EUC0603"))
    )
    (comp (ref "C320")
      (value "15p")
      (footprint "eagle-import:C0603")
      (libsource (lib "eagle-import") (part "C-EUC0603"))
    )
    (comp (ref "C321")
      (value "15p")
      (footprint "eagle-import:C0603")
      (libsource (lib "eagle-import") (part "C-EUC0603"))
    )
    (comp (ref "C350")
      (value "1p8")
      (footprint "eagle-import:C0603K")
      (libsource (lib "eagle-import") (part "C-EUC0603K"))
    )
    (comp (ref "C351")
      (value "100p")
      (footprint "eagle-import:C0603")
      (libsource (lib "eagle-import") (part "C-EUC0603"))
    )
    (comp (ref "C352")
      (value "100p")
      (footprint "eagle-import:C0603K")
      (libsource (lib "eagle-import") (part "C-EUC0603K"))
    )
    (comp (ref "F300")
      (value "2450BM15A0002")
      (footprint "eagle-import:2450BM15A0002")
      (libsource (lib "eagle-import") (part "2450BM15A0002"))
    )
    (comp (ref "IC300")
      (value "CC110L_RTK_20")
      (footprint "eagle-import:RTK20_2P4X2P4")
      (fields (field (name "GENERIC_PART_NUMBER") "CC110L") (field (name "MANUFACTURER") "Texas Instruments"))
      (libsource (lib "eagle-import") (part "CC110L_RTK_20"))
    )
    (comp (ref "L350")
      (value "5n6")
      (footprint "eagle-import:L2012C")
      (libsource (lib "eagle-import") (part "L-EUL2012C"))
    )
    (comp (ref "R300")
      (value "56k")
      (footprint "eagle-import:R0603")
      (libsource (lib "eagle-import") (part "R-EU_R0603"))
    )
    (comp (ref "U$1")
      (value "ANTENNA868W3013-INV")
      (footprint "eagle-import:W3013-INV")
      (libsource (lib "eagle-import") (part "ANTENNA868W3013-INV"))
    )
    (comp (ref "X320")
      (value "CRYSTAL.3.2X2.5MM")
      (footprint "eagle-import:3.2X2.5MM")
      (fields (field (name "OC_FARNELL") "unknown"))
      (libsource (lib "eagle-import") (part "CRYSTAL.3.2X2.5MM"))
    )
    (comp (ref "C700")
      (value "100n")
      (footprint "eagle-import:C0603")
      (fields (field (name "MF") "STMICROELECTRONICS") (field (name "MPN") "STP100NF04"))
      (libsource (lib "eagle-import") (part "C-EUC0603"))
    )
    (comp (ref "IC700")
      (value "Value")
      (footprint "eagle-import:DDC0006A_N")
      (fields (field (name "MANUFACTURER") "Texas Instruments") (field (name "PARTNUMBER") "TPL5110DDC"))
      (libsource (lib "eagle-import") (part "TPL5110DDCR"))
    )
    (comp (ref "R700")
      (value "18k75")
      (footprint "eagle-import:R0603")
      (libsource (lib "eagle-import") (part "R-EU_R0603"))
    )
    (comp (ref "R710")
      (value "0")
      (footprint "eagle-import:R0603")
      (libsource (lib "eagle-import") (part "R-EU_R0603"))
    )
    (comp (ref "R711")
      (value "DNB")
      (footprint "eagle-import:R0603")
      (libsource (lib "eagle-import") (part "R-EU_R0603"))
    )
    (comp (ref "R712")
      (value "100k")
      (footprint "eagle-import:R0603")
      (libsource (lib "eagle-import") (part "R-EU_R0603"))
    )
    (comp (ref "S1")
      (value "SKHMPSE010")
      (footprint "eagle-import:SKHMPXE010")
      (libsource (lib "eagle-import") (part "SKHMPE010S"))
    )
  )
  (nets
    (net (code "1") (name "ADRESS_0") (class "Default")
      (node (ref "ADR0") (pin "2") (pinfunction "2_2") (pintype "passive"))
      (node (ref "IC500") (pin "8") (pinfunction "P1.3/TA1.2/UCB0STE/A3*/CD3_8") (pintype "bidirectional"))
    )
    (net (code "2") (name "ADRESS_1") (class "Default")
      (node (ref "ADR1") (pin "2") (pinfunction "2_2") (pintype "passive"))
      (node (ref "IC500") (pin "7") (pinfunction "P3.3/A15*/CD15_7") (pintype "bidirectional"))
    )
    (net (code "3") (name "ADRESS_2") (class "Default")
      (node (ref "ADR2") (pin "2") (pinfunction "2_2") (pintype "passive"))
      (node (ref "IC500") (pin "6") (pinfunction "P3.2/A14*/CD14_6") (pintype "bidirectional"))
    )
    (net (code "4") (name "BQ25570_VBAT_OK") (class "Default")
      (node (ref "IC200") (pin "13") (pinfunction "VBAT_OK_13") (pintype "output"))
      (node (ref "IC500") (pin "5") (pinfunction "P3.1/A13*/CD13_5") (pintype "bidirectional"))
    )
    (net (code "5") (name "BQ25570_VSTOR") (class "Default")
      (node (ref "C240") (pin "2") (pinfunction "2_2") (pintype "passive"))
      (node (ref "C241") (pin "2") (pinfunction "2_2") (pintype "passive"))
      (node (ref "C700") (pin "1") (pinfunction "1_1") (pintype "passive"))
      (node (ref "IC200") (pin "19") (pinfunction "VSTOR_19") (pintype "power_in"))
      (node (ref "IC200") (pin "3") (pinfunction "VOC_SAMP_3") (pintype "input"))
      (node (ref "IC700") (pin "1") (pinfunction "VDD_1") (pintype "power_in"))
      (node (ref "R200") (pin "1") (pinfunction "1_1") (pintype "passive"))
      (node (ref "R710") (pin "2") (pinfunction "2_2") (pintype "passive"))
      (node (ref "S1") (pin "3") (pinfunction "2.1_3") (pintype "passive"))
      (node (ref "S1") (pin "4") (pinfunction "2.2_4") (pintype "passive"))
    )
    (net (code "6") (name "CC110L_GDO0") (class "Default")
      (node (ref "IC300") (pin "6") (pinfunction "GDO0_6") (pintype "output"))
      (node (ref "IC500") (pin "17") (pinfunction "P2.5/TB0.0/UCA1TXD/UCA1SIMO_17") (pintype "bidirectional"))
    )
    (net (code "7") (name "CC110L_GDO2") (class "Default")
      (node (ref "IC300") (pin "3") (pinfunction "GDO2_3") (pintype "output"))
      (node (ref "IC500") (pin "18") (pinfunction "P2.6/TB1.0/UCA1RXD/UCA1SOMI_18") (pintype "bidirectional"))
    )
    (net (code "8") (name "DEVICE_0") (class "Default")
      (node (ref "DEV0") (pin "2") (pinfunction "2_2") (pintype "passive"))
      (node (ref "IC500") (pin "11") (pinfunction "PJ.0/TDO/TB0OUTH/SMCLK/CD6_11") (pintype "bidirectional"))
    )
    (net (code "9") (name "DEVICE_1") (class "Default")
      (node (ref "DEV1") (pin "2") (pinfunction "2_2") (pintype "passive"))
      (node (ref "IC500") (pin "12") (pinfunction "PJ.1/TDI/TCLK/TB1OUTH/MCLK/CD7_12") (pintype "bidirectional"))
    )
    (net (code "10") (name "GND") (class "Default")
      (node (ref "ADR0") (pin "1") (pinfunction "1_1") (pintype "passive"))
      (node (ref "ADR1") (pin "1") (pinfunction "1_1") (pintype "passive"))
      (node (ref "ADR2") (pin "1") (pinfunction "1_1") (pintype "passive"))
      (node (ref "BAT") (pin "P$2") (pinfunction "2_P$2") (pintype "passive"))
      (node (ref "C100") (pin "2") (pinfunction "2_2") (pintype "passive"))
      (node (ref "C101") (pin "2") (pinfunction "2_2") (pintype "passive"))
      (node (ref "C200") (pin "2") (pinfunction "2_2") (pintype "passive"))
      (node (ref "C201") (pin "2") (pinfunction "2_2") (pintype "passive"))
      (node (ref "C210") (pin "2") (pinfunction "2_2") (pintype "passive"))
      (node (ref "C240") (pin "1") (pinfunction "1_1") (pintype "passive"))
      (node (ref "C241") (pin "1") (pinfunction "1_1") (pintype "passive"))
      (node (ref "C300") (pin "2") (pinfunction "2_2") (pintype "passive"))
      (node (ref "C301") (pin "2") (pinfunction "2_2") (pintype "passive"))
      (node (ref "C302") (pin "2") (pinfunction "2_2") (pintype "passive"))
      (node (ref "C310") (pin "2") (pinfunction "2_2") (pintype "passive"))
      (node (ref "C320") (pin "2") (pinfunction "2_2") (pintype "passive"))
      (node (ref "C321") (pin "2") (pinfunction "2_2") (pintype "passive"))
      (node (ref "C350") (pin "1") (pinfunction "1_1") (pintype "passive"))
      (node (ref "C352") (pin "2") (pinfunction "2_2") (pintype "passive"))
      (node (ref "C400") (pin "2") (pinfunction "2_2") (pintype "passive"))
      (node (ref "C500") (pin "2") (pinfunction "2_2") (pintype "passive"))
      (node (ref "C501") (pin "2") (pinfunction "2_2") (pintype "passive"))
      (node (ref "C510") (pin "2") (pinfunction "2_2") (pintype "passive"))
      (node (ref "C600") (pin "2") (pinfunction "2_2") (pintype "passive"))
      (node (ref "C700") (pin "2") (pinfunction "2_2") (pintype "passive"))
      (node (ref "C800") (pin "2") (pinfunction "2_2") (pintype "passive"))
      (node (ref "DEV0") (pin "1") (pinfunction "1_1") (pintype "passive"))
      (node (ref "DEV1") (pin "1") (pinfunction "1_1") (pintype "passive"))
      (node (ref "F300") (pin "2") (pinfunction "GND_2") (pintype "passive"))
      (node (ref "F300") (pin "5") (pinfunction "GND_5") (pintype "passive"))
      (node (ref "F300") (pin "6") (pinfunction "GND_6") (pintype "passive"))
      (node (ref "IC100") (pin "3") (pinfunction "RGND_3") (pintype "bidirectional"))
      (node (ref "IC100") (pin "5") (pinfunction "SA0_5") (pintype "bidirectional"))
      (node (ref "IC100") (pin "8") (pinfunction "GND_8") (pintype "power_in"))
      (node (ref "IC100") (pin "9") (pinfunction "GND_9") (pintype "power_in"))
      (node (ref "IC200") (pin "1") (pinfunction "VSS_2_1") (pintype "power_in"))
      (node (ref "IC200") (pin "15") (pinfunction "VSS_15") (pintype "power_in"))
      (node (ref "IC200") (pin "17") (pinfunction "NC_17") (pintype "passive"))
      (node (ref "IC200") (pin "21") (pinfunction "PAD_21") (pintype "power_in"))
      (node (ref "IC200") (pin "5") (pinfunction "EN_N_5") (pintype "input"))
      (node (ref "IC200") (pin "9") (pinfunction "NC_2_9") (pintype "power_in"))
      (node (ref "IC300") (pin "16") (pinfunction "GND_2_16") (pintype "power_in"))
      (node (ref "IC300") (pin "19") (pinfunction "GND_19") (pintype "power_in"))
      (node (ref "IC300") (pin "21") (pinfunction "EPAD_21") (pintype "power_in"))
      (node (ref "IC400") (pin "B2") (pinfunction "GND_B2") (pintype "power_in"))
      (node (ref "IC400") (pin "C1") (pinfunction "ADR0_C1") (pintype "input"))
      (node (ref "IC400") (pin "D1") (pinfunction "ADR1_D1") (pintype "input"))
      (node (ref "IC500") (pin "31") (pinfunction "DVSS_31") (pintype "power_in"))
      (node (ref "IC500") (pin "36") (pinfunction "AVSS_2_36") (pintype "power_in"))
      (node (ref "IC500") (pin "39") (pinfunction "AVSS_39") (pintype "power_in"))
      (node (ref "IC500") (pin "41") (pinfunction "EPAD_41") (pintype "passive"))
      (node (ref "IC600") (pin "2") (pinfunction "GND_2") (pintype "power_in"))
      (node (ref "IC600") (pin "4") (pinfunction "ADD0_4") (pintype "input"))
      (node (ref "IC700") (pin "2") (pinfunction "GND_2") (pintype "power_in"))
      (node (ref "IC800") (pin "A1") (pinfunction "CTG_A1") (pintype "passive"))
      (node (ref "IC800") (pin "A4") (pinfunction "GND_A4") (pintype "power_in"))
      (node (ref "IC800") (pin "B3") (pinfunction "QSTRT_B3") (pintype "input"))
      (node (ref "LINK") (pin "2") (pinfunction "2_2") (pintype "passive"))
      (node (ref "PROG") (pin "4") (pinfunction "4_4") (pintype "passive"))
      (node (ref "R211") (pin "1") (pinfunction "1_1") (pintype "passive"))
      (node (ref "R222") (pin "1") (pinfunction "1_1") (pintype "passive"))
      (node (ref "R231") (pin "1") (pinfunction "1_1") (pintype "passive"))
      (node (ref "R300") (pin "1") (pinfunction "1_1") (pintype "passive"))
      (node (ref "R700") (pin "2") (pinfunction "2_2") (pintype "passive"))
      (node (ref "R711") (pin "1") (pinfunction "1_1") (pintype "passive"))
      (node (ref "R712") (pin "1") (pinfunction "1_1") (pintype "passive"))
      (node (ref "S1") (pin "5") (pinfunction "SH_5") (pintype "passive"))
      (node (ref "U$1") (pin "2") (pinfunction "P$2_2") (pintype "bidirectional"))
      (node (ref "U$1") (pin "3") (pinfunction "P$2_3") (pintype "bidirectional"))
      (node (ref "X320") (pin "2") (pinfunction "P$1_2") (pintype "bidirectional"))
      (node (ref "X320") (pin "4") (pinfunction "P$1_4") (pintype "bidirectional"))
    )
    (net (code "11") (name "LPS25H_INT") (class "Default")
      (node (ref "IC100") (pin "7") (pinfunction "INT_7") (pintype "bidirectional"))
      (node (ref "IC500") (pin "4") (pinfunction "P3.0/A12*/CD12_4") (pintype "bidirectional"))
    )
    (net (code "12") (name "MSP430_CLK") (class "Default")
      (node (ref "IC300") (pin "1") (pinfunction "SCLK1_1") (pintype "passive"))
      (node (ref "IC500") (pin "10") (pinfunction "P1.5/TB0.2/UCA0CLK/A5*/CD5_10") (pintype "bidirectional"))
    )
    (net (code "13") (name "MSP430_MISO") (class "Default")
      (node (ref "IC300") (pin "2") (pinfunction "SO_2") (pintype "output"))
      (node (ref "IC500") (pin "22") (pinfunction "P2.1/TB2.1/UCA0RXD/UCA0SOMI/TB0.0_22") (pintype "bidirectional"))
    )
    (net (code "14") (name "MSP430_MOSI") (class "Default")
      (node (ref "IC300") (pin "20") (pinfunction "SI_20") (pintype "input"))
      (node (ref "IC500") (pin "21") (pinfunction "P2.0/TB2.0/UCA0TXD/UCA0SIMO/TB0CLK/ACLK_21") (pintype "bidirectional"))
    )
    (net (code "15") (name "MSP430_SCL") (class "Default")
      (node (ref "IC100") (pin "2") (pinfunction "SCL_2") (pintype "bidirectional"))
      (node (ref "IC400") (pin "A1") (pinfunction "SCL_A1") (pintype "input"))
      (node (ref "IC500") (pin "29") (pinfunction "P1.7/TB1.2/UCB0SOMI/UCB0SCL/TA1.0_29") (pintype "bidirectional"))
      (node (ref "IC600") (pin "1") (pinfunction "SCL_1") (pintype "bidirectional"))
      (node (ref "IC800") (pin "B2") (pinfunction "SCL_B2") (pintype "input"))
      (node (ref "LINK") (pin "5") (pinfunction "5_5") (pintype "passive"))
    )
    (net (code "16") (name "MSP430_SDA") (class "Default")
      (node (ref "IC100") (pin "4") (pinfunction "SDA_4") (pintype "bidirectional"))
      (node (ref "IC400") (pin "A2") (pinfunction "SDA_A2") (pintype "bidirectional"))
      (node (ref "IC500") (pin "28") (pinfunction "P1.6/TB1.1/UCB0SIMO/UCB0SDA/TA0.0_28") (pintype "bidirectional"))
      (node (ref "IC600") (pin "6") (pinfunction "SDA_6") (pintype "bidirectional"))
      (node (ref "IC800") (pin "B1") (pinfunction "SDA_B1") (pintype "bidirectional"))
      (node (ref "LINK") (pin "4") (pinfunction "4_4") (pintype "passive"))
    )
    (net (code "17") (name "MSP430_TEST") (class "Default")
      (node (ref "IC500") (pin "19") (pinfunction "TEST/SBWTCK_19") (pintype "bidirectional"))
      (node (ref "PROG") (pin "2") (pinfunction "2_2") (pintype "passive"))
    )
    (net (code "18") (name "MSP430_VCORE") (class "Default")
      (node (ref "C510") (pin "1") (pinfunction "1_1") (pintype "passive"))
      (node (ref "IC500") (pin "30") (pinfunction "VCORE_30") (pintype "power_in"))
    )
    (net (code "19") (name "Net-(C350-Pad2)") (class "Default")
      (node (ref "C350") (pin "2") (pinfunction "2_2") (pintype "passive"))
      (node (ref "C351") (pin "2") (pinfunction "2_2") (pintype "passive"))
      (node (ref "L350") (pin "2") (pinfunction "2_2") (pintype "passive"))
    )
    (net (code "20") (name "Net-(F300-UNBAL)") (class "Default")
      (node (ref "F300") (pin "1") (pinfunction "UNBAL_1") (pintype "passive"))
      (node (ref "L350") (pin "1") (pinfunction "1_1") (pintype "passive"))
    )
    (net (code "21") (name "Net-(IC200-LBOOST)") (class "Default")
      (node (ref "IC200") (pin "20") (pinfunction "LBOOST_20") (pintype "input"))
      (node (ref "L200") (pin "P$2") (pinfunction "2_P$2") (pintype "passive"))
    )
    (net (code "22") (name "Net-(IC200-LBUCK)") (class "Default")
      (node (ref "IC200") (pin "16") (pinfunction "LBUCK_16") (pintype "passive"))
      (node (ref "L210") (pin "P$1") (pinfunction "1_P$1") (pintype "passive"))
    )
    (net (code "23") (name "Net-(IC200-OK_HYST)") (class "Default")
      (node (ref "IC200") (pin "10") (pinfunction "OK_HYST_10") (pintype "input"))
      (node (ref "R220") (pin "1") (pinfunction "1_1") (pintype "passive"))
      (node (ref "R221") (pin "2") (pinfunction "2_2") (pintype "passive"))
    )
    (net (code "24") (name "Net-(IC200-OK_PROG)") (class "Default")
      (node (ref "IC200") (pin "11") (pinfunction "OK_PROG_11") (pintype "input"))
      (node (ref "R221") (pin "1") (pinfunction "1_1") (pintype "passive"))
      (node (ref "R222") (pin "2") (pinfunction "2_2") (pintype "passive"))
    )
    (net (code "25") (name "Net-(IC200-VBAT_OV)") (class "Default")
      (node (ref "IC200") (pin "7") (pinfunction "VBAT_OV_7") (pintype "input"))
      (node (ref "R210") (pin "2") (pinfunction "2_2") (pintype "passive"))
      (node (ref "R211") (pin "2") (pinfunction "2_2") (pintype "passive"))
    )
    (net (code "26") (name "Net-(IC200-VOUT)") (class "Default")
      (node (ref "!PROG") (pin "2") (pinfunction "2_2") (pintype "passive"))
      (node (ref "C210") (pin "1") (pinfunction "1_1") (pintype "passive"))
      (node (ref "IC200") (pin "14") (pinfunction "VOUT_14") (pintype "power_in"))
      (node (ref "L210") (pin "P$2") (pinfunction "2_P$2") (pintype "passive"))
    )
    (net (code "27") (name "Net-(IC200-VOUT_EN)") (class "Default")
      (node (ref "IC200") (pin "6") (pinfunction "VOUT_EN_6") (pintype "input"))
      (node (ref "R200") (pin "2") (pinfunction "2_2") (pintype "passive"))
      (node (ref "R201") (pin "1") (pinfunction "1_1") (pintype "passive"))
    )
    (net (code "28") (name "Net-(IC200-VOUT_SET)") (class "Default")
      (node (ref "IC200") (pin "12") (pinfunction "VOUT_SET_12") (pintype "input"))
      (node (ref "R230") (pin "1") (pinfunction "1_1") (pintype "passive"))
      (node (ref "R231") (pin "2") (pinfunction "2_2") (pintype "passive"))
    )
    (net (code "29") (name "Net-(IC200-VRDIV)") (class "Default")
      (node (ref "IC200") (pin "8") (pinfunction "VRDIV_8") (pintype "output"))
      (node (ref "R210") (pin "1") (pinfunction "1_1") (pintype "passive"))
      (node (ref "R220") (pin "2") (pinfunction "2_2") (pintype "passive"))
      (node (ref "R230") (pin "2") (pinfunction "2_2") (pintype "passive"))
    )
    (net (code "30") (name "Net-(IC200-VREF_SAMP)") (class "Default")
      (node (ref "C200") (pin "1") (pinfunction "1_1") (pintype "passive"))
      (node (ref "IC200") (pin "4") (pinfunction "VREF_SAMP_4") (pintype "input"))
    )
    (net (code "31") (name "Net-(IC300-DCOUPL)") (class "Default")
      (node (ref "C310") (pin "1") (pinfunction "1_1") (pintype "passive"))
      (node (ref "IC300") (pin "5") (pinfunction "DCOUPL_5") (pintype "passive"))
    )
    (net (code "32") (name "Net-(IC300-RBIAS)") (class "Default")
      (node (ref "IC300") (pin "17") (pinfunction "RBIAS_17") (pintype "passive"))
      (node (ref "R300") (pin "2") (pinfunction "2_2") (pintype "passive"))
    )
    (net (code "33") (name "Net-(IC300-RF_N)") (class "Default")
      (node (ref "F300") (pin "3") (pinfunction "BAL_3") (pintype "passive"))
      (node (ref "IC300") (pin "13") (pinfunction "RF_N_13") (pintype "passive"))
    )
    (net (code "34") (name "Net-(IC300-RF_P)") (class "Default")
      (node (ref "F300") (pin "4") (pinfunction "BAL_4") (pintype "passive"))
      (node (ref "IC300") (pin "12") (pinfunction "RF_P_12") (pintype "passive"))
    )
    (net (code "35") (name "Net-(IC300-XOSC_Q1)") (class "Default")
      (node (ref "C320") (pin "1") (pinfunction "1_1") (pintype "passive"))
      (node (ref "IC300") (pin "8") (pinfunction "XOSC_Q1_8") (pintype "passive"))
      (node (ref "X320") (pin "3") (pinfunction "2_3") (pintype "passive"))
    )
    (net (code "36") (name "Net-(IC300-XOSC_Q2)") (class "Default")
      (node (ref "C321") (pin "1") (pinfunction "1_1") (pintype "passive"))
      (node (ref "IC300") (pin "10") (pinfunction "XOSC_Q2_10") (pintype "passive"))
      (node (ref "X320") (pin "1") (pinfunction "1_1") (pintype "passive"))
    )
    (net (code "37") (name "Net-(IC700-DELAY_M_DRV)") (class "Default")
      (node (ref "IC700") (pin "3") (pinfunction "DELAY_M_DRV_3") (pintype "input"))
      (node (ref "R700") (pin "1") (pinfunction "1_1") (pintype "passive"))
      (node (ref "S1") (pin "1") (pinfunction "1.1_1") (pintype "passive"))
      (node (ref "S1") (pin "2") (pinfunction "1.2_2") (pintype "passive"))
    )
    (net (code "38") (name "Net-(IC700-EN_ONE_SHOT)") (class "Default")
      (node (ref "IC700") (pin "6") (pinfunction "EN_ONE_SHOT_6") (pintype "output"))
      (node (ref "R710") (pin "1") (pinfunction "1_1") (pintype "passive"))
      (node (ref "R711") (pin "2") (pinfunction "2_2") (pintype "passive"))
    )
    (net (code "39") (name "Net-(U$1-P$1)") (class "Default")
      (node (ref "C351") (pin "1") (pinfunction "1_1") (pintype "passive"))
      (node (ref "C352") (pin "1") (pinfunction "1_1") (pintype "passive"))
      (node (ref "U$1") (pin "1") (pinfunction "P$1_1") (pintype "bidirectional"))
    )
    (net (code "40") (name "SOLAR_P") (class "Default")
      (node (ref "C201") (pin "1") (pinfunction "1_1") (pintype "passive"))
      (node (ref "IC200") (pin "2") (pinfunction "VIN_DC_2") (pintype "power_in"))
      (node (ref "IC500") (pin "34") (pinfunction "P2.3/TA0.0/UCA1STE/A6*/CD10_34") (pintype "bidirectional"))
      (node (ref "L200") (pin "P$1") (pinfunction "1_P$1") (pintype "passive"))
      (node (ref "LINK") (pin "1") (pinfunction "1_1") (pintype "passive"))
    )
    (net (code "41") (name "TPL5111_DONE") (class "Default")
      (node (ref "IC500") (pin "27") (pinfunction "P3.7/TB2.2_27") (pintype "bidirectional"))
      (node (ref "IC700") (pin "4") (pinfunction "DONE_4") (pintype "input"))
      (node (ref "R712") (pin "2") (pinfunction "2_2") (pintype "passive"))
    )
    (net (code "42") (name "TPL5111_DRV") (class "Default")
      (node (ref "IC700") (pin "5") (pinfunction "DRV_5") (pintype "output"))
      (node (ref "R201") (pin "2") (pinfunction "2_2") (pintype "passive"))
    )
    (net (code "43") (name "VBAT") (class "Default")
      (node (ref "BAT") (pin "P$1") (pinfunction "1_P$1") (pintype "passive"))
      (node (ref "C800") (pin "1") (pinfunction "1_1") (pintype "passive"))
      (node (ref "IC200") (pin "18") (pinfunction "VBAT_18") (pintype "bidirectional"))
      (node (ref "IC500") (pin "35") (pinfunction "P2.4/TA1.0/UCA1CLK/A7*/CD11_35") (pintype "bidirectional"))
      (node (ref "IC800") (pin "A2") (pinfunction "CELL_A2") (pintype "passive"))
      (node (ref "IC800") (pin "A3") (pinfunction "VDD_A3") (pintype "power_in"))
    )
    (net (code "44") (name "VCC") (class "Default")
      (node (ref "!PROG") (pin "1") (pinfunction "1_1") (pintype "passive"))
      (node (ref "C100") (pin "1") (pinfunction "1_1") (pintype "passive"))
      (node (ref "C101") (pin "1") (pinfunction "1_1") (pintype "passive"))
      (node (ref "C300") (pin "1") (pinfunction "1_1") (pintype "passive"))
      (node (ref "C301") (pin "1") (pinfunction "1_1") (pintype "passive"))
      (node (ref "C302") (pin "1") (pinfunction "1_1") (pintype "passive"))
      (node (ref "C400") (pin "1") (pinfunction "1_1") (pintype "passive"))
      (node (ref "C500") (pin "1") (pinfunction "1_1") (pintype "passive"))
      (node (ref "C501") (pin "1") (pinfunction "1_1") (pintype "passive"))
      (node (ref "C600") (pin "1") (pinfunction "1_1") (pintype "passive"))
      (node (ref "IC100") (pin "1") (pinfunction "VDD_IO_1") (pintype "power_in"))
      (node (ref "IC100") (pin "10") (pinfunction "VDD_10") (pintype "power_in"))
      (node (ref "IC100") (pin "6") (pinfunction "CS_6") (pintype "bidirectional"))
      (node (ref "IC300") (pin "11") (pinfunction "AVDD_3_11") (pintype "power_in"))
      (node (ref "IC300") (pin "14") (pinfunction "AVDD_4_14") (pintype "power_in"))
      (node (ref "IC300") (pin "15") (pinfunction "AVDD_15") (pintype "power_in"))
      (node (ref "IC300") (pin "18") (pinfunction "DGUARD_18") (pintype "passive"))
      (node (ref "IC300") (pin "4") (pinfunction "DVDD_4") (pintype "power_in"))
      (node (ref "IC300") (pin "9") (pinfunction "AVDD_2_9") (pintype "power_in"))
      (node (ref "IC400") (pin "B1") (pinfunction "VDD_B1") (pintype "power_in"))
      (node (ref "IC500") (pin "32") (pinfunction "DVCC_32") (pintype "power_in"))
      (node (ref "IC500") (pin "40") (pinfunction "AVCC_40") (pintype "power_in"))
      (node (ref "IC600") (pin "5") (pinfunction "V+_5") (pintype "power_in"))
      (node (ref "LINK") (pin "3") (pinfunction "3_3") (pintype "passive"))
      (node (ref "PROG") (pin "1") (pinfunction "1_1") (pintype "passive"))
      (node (ref "R500") (pin "2") (pinfunction "2_2") (pintype "passive"))
    )
    (net (code "45") (name "unconnected-(IC400-DNC-PadC2)") (class "Default")
      (node (ref "IC400") (pin "C2") (pinfunction "DNC_C2") (pintype "passive"))
    )
    (net (code "46") (name "unconnected-(IC500-P2.2{slash}TB2.2{slash}UCB0CLK{slash}TB1.0-Pad23)") (class "Default")
      (node (ref "IC500") (pin "23") (pinfunction "P2.2/TB2.2/UCB0CLK/TB1.0_23") (pintype "bidirectional"))
    )
    (net (code "47") (name "unconnected-(IC500-P2.7-Pad33)") (class "Default")
      (node (ref "IC500") (pin "33") (pinfunction "P2.7_33") (pintype "bidirectional"))
    )
    (net (code "48") (name "unconnected-(IC500-P3.4{slash}TB1.1{slash}TB2CLK{slash}SMCLK-Pad24)") (class "Default")
      (node (ref "IC500") (pin "24") (pinfunction "P3.4/TB1.1/TB2CLK/SMCLK_24") (pintype "bidirectional"))
    )
    (net (code "49") (name "unconnected-(IC500-P3.5{slash}TB1.2{slash}CDOUT-Pad25)") (class "Default")
      (node (ref "IC500") (pin "25") (pinfunction "P3.5/TB1.2/CDOUT_25") (pintype "bidirectional"))
    )
    (net (code "50") (name "unconnected-(IC500-P3.6{slash}TB2.1{slash}TB1CLK-Pad26)") (class "Default")
      (node (ref "IC500") (pin "26") (pinfunction "P3.6/TB2.1/TB1CLK_26") (pintype "bidirectional"))
    )
    (net (code "51") (name "unconnected-(IC500-P4.0{slash}TB2.0-Pad15)") (class "Default")
      (node (ref "IC500") (pin "15") (pinfunction "P4.0/TB2.0_15") (pintype "bidirectional"))
    )
    (net (code "52") (name "unconnected-(IC500-PJ.2{slash}TMS{slash}TB2OUTH{slash}ACLK{slash}CD8-Pad13)") (class "Default")
      (node (ref "IC500") (pin "13") (pinfunction "PJ.2/TMS/TB2OUTH/ACLK/CD8_13") (pintype "bidirectional"))
    )
    (net (code "53") (name "unconnected-(IC500-PJ.3{slash}TCK{slash}CD9-Pad14)") (class "Default")
      (node (ref "IC500") (pin "14") (pinfunction "PJ.3/TCK/CD9_14") (pintype "bidirectional"))
    )
    (net (code "54") (name "unconnected-(IC500-PJ.4{slash}XIN-Pad37)") (class "Default")
      (node (ref "IC500") (pin "37") (pinfunction "PJ.4/XIN_37") (pintype "bidirectional"))
    )
    (net (code "55") (name "unconnected-(IC500-PJ.5{slash}XOUT-Pad38)") (class "Default")
      (node (ref "IC500") (pin "38") (pinfunction "PJ.5/XOUT_38") (pintype "bidirectional"))
    )
    (net (code "56") (name "~{CC110L_CS}") (class "Default")
      (node (ref "IC300") (pin "7") (pinfunction "CSN_7") (pintype "passive"))
      (node (ref "IC500") (pin "9") (pinfunction "P1.4/TB0.1/UCA0STE/A4*/CD4_9") (pintype "bidirectional"))
    )
    (net (code "57") (name "~{HDC1000_INT}") (class "Default")
      (node (ref "IC400") (pin "D2") (pinfunction "DRDY_N_D2") (pintype "input"))
      (node (ref "IC500") (pin "3") (pinfunction "P1.2/TA1.1/TA0CLK/CDOUT/A2*/CD2_3") (pintype "bidirectional"))
    )
    (net (code "58") (name "~{LINK_INT}") (class "Default")
      (node (ref "IC500") (pin "1") (pinfunction "P1.0/TA0.1/DMAE0/RTCCLK/A0*/CD0/VEREF-*_1") (pintype "bidirectional"))
      (node (ref "LINK") (pin "6") (pinfunction "6_6") (pintype "passive"))
    )
    (net (code "59") (name "~{MAX17048_ALERT}") (class "Default")
      (node (ref "IC500") (pin "16") (pinfunction "P4.1_16") (pintype "bidirectional"))
      (node (ref "IC800") (pin "B4") (pinfunction "*ALRT_B4") (pintype "output"))
    )
    (net (code "60") (name "~{MSP430_RST}") (class "Default")
      (node (ref "IC500") (pin "20") (pinfunction "*RST/NMI/SBWTDIO_20") (pintype "bidirectional"))
      (node (ref "PROG") (pin "3") (pinfunction "3_3") (pintype "passive"))
      (node (ref "R500") (pin "1") (pinfunction "1_1") (pintype "passive"))
    )
    (net (code "61") (name "~{TMP102_ALERT}") (class "Default")
      (node (ref "IC500") (pin "2") (pinfunction "P1.1/TA0.2/TA1CLK/CDOUT/A1*/CD1/VEREF+*_2") (pintype "bidirectional"))
      (node (ref "IC600") (pin "3") (pinfunction "ALERT_3") (pintype "output"))
    )
  )
)
